# Mayfly_v1p0_revA3_public.net
KiCad netlist of a schematic drawn in EAGLE
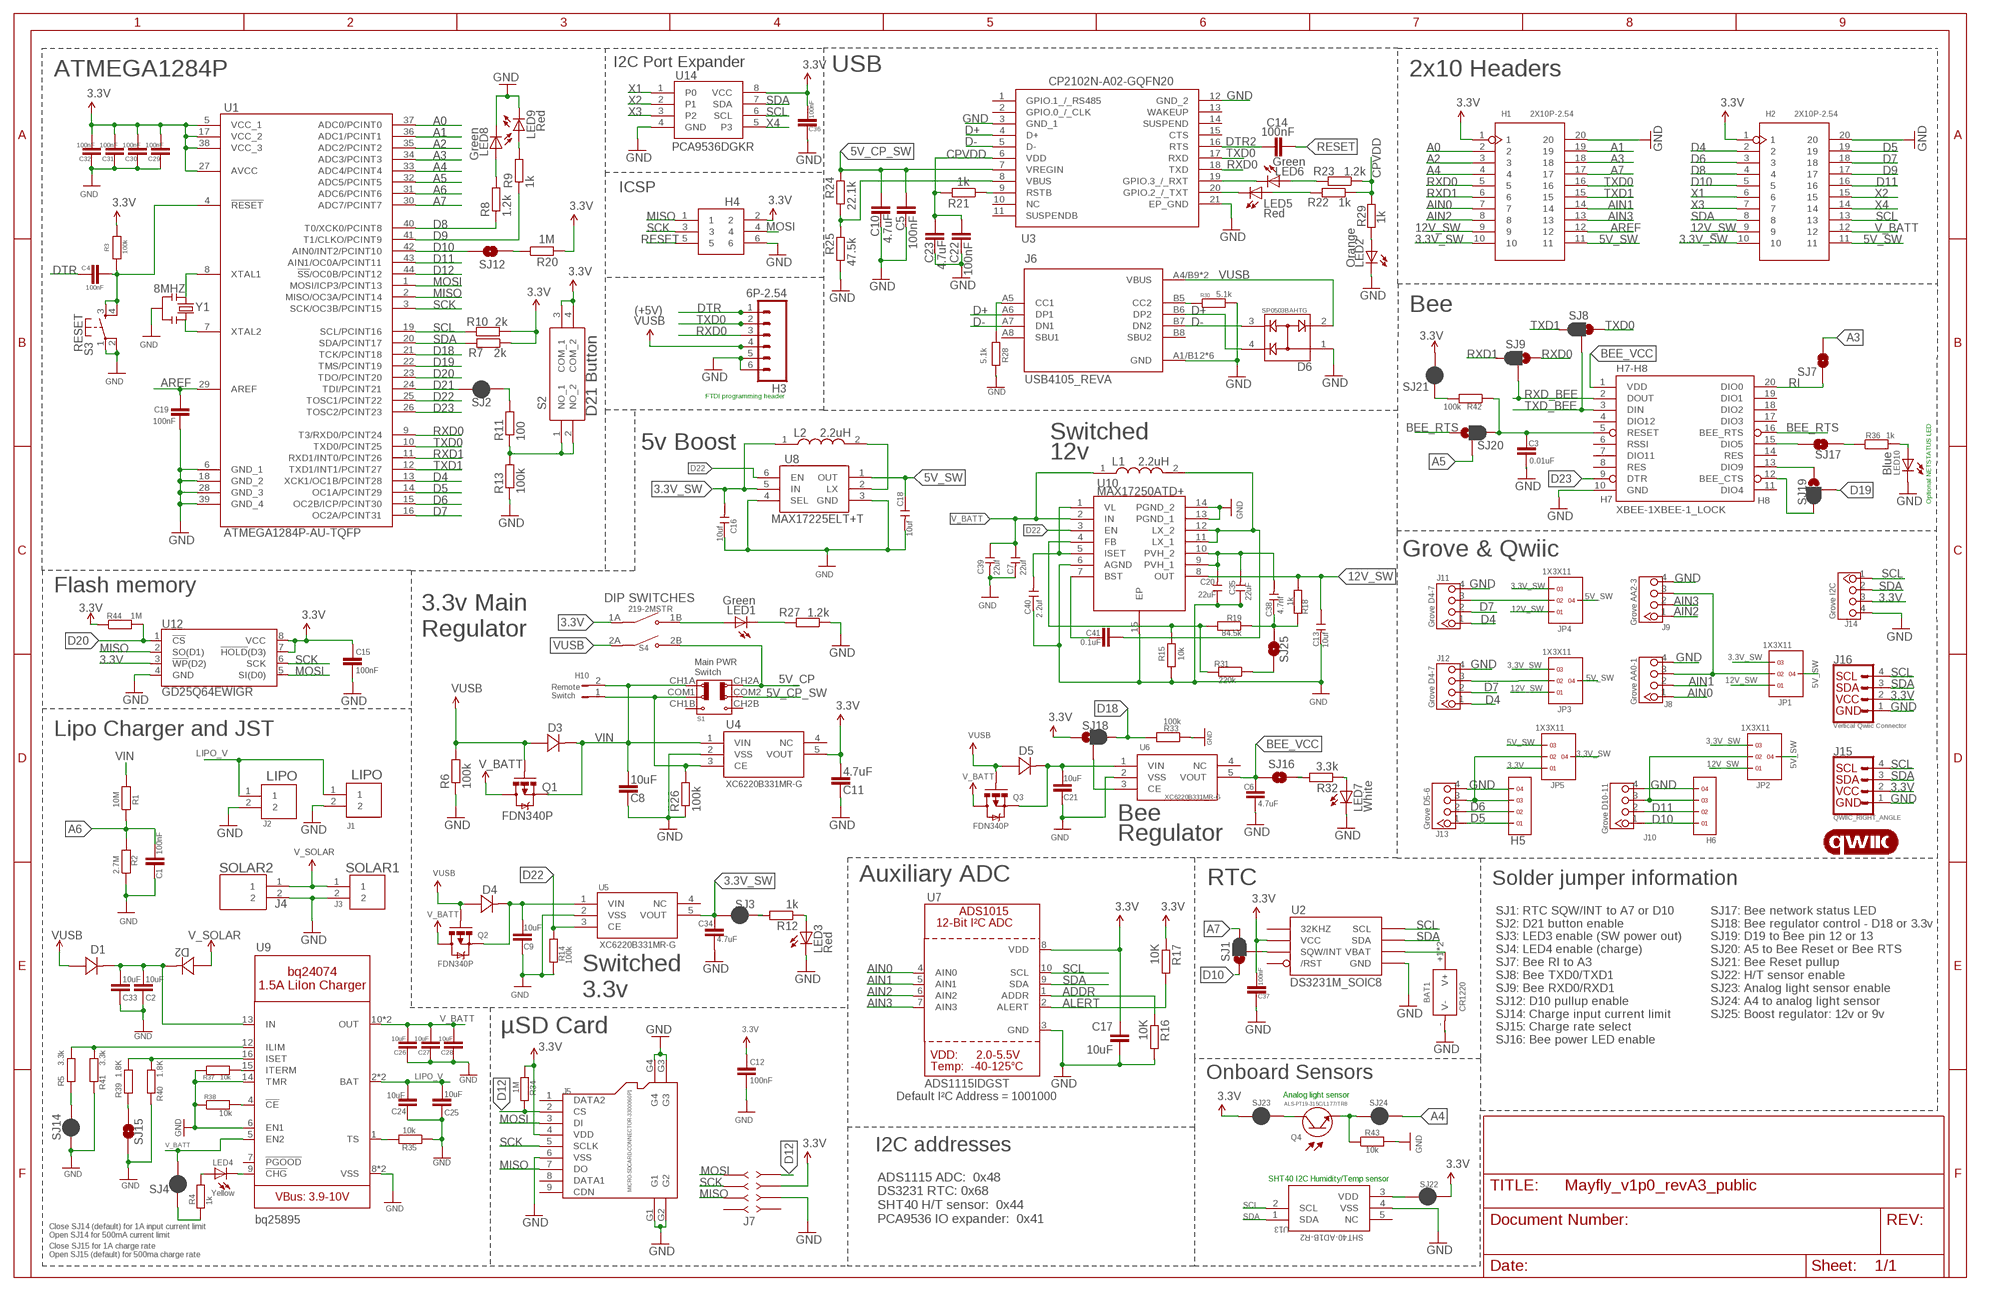
[diagram p0: schematic, sheet 1]

(export (version "E")
  (design (tool "Eeschema 10.0.6"))
  (components
    (comp (ref "BAT1")
      (value "CR1220")
      (footprint "eagle-import:BAT2P-13.5-CR1220")
      (libsource (lib "eagle-import") (part "DIP-BATTERY-CELL-HOLDER(1220)"))
    )
    (comp (ref "C1")
      (value "100nF")
      (footprint "eagle-import:C0603")
      (libsource (lib "eagle-import") (part "C_0603"))
    )
    (comp (ref "C2")
      (value "10uF")
      (footprint "eagle-import:C0603")
      (libsource (lib "eagle-import") (part "C_0603"))
    )
    (comp (ref "C3")
      (value "0.01uF")
      (footprint "eagle-import:C0603")
      (libsource (lib "eagle-import") (part "C_0603"))
    )
    (comp (ref "C4")
      (value "100nF")
      (footprint "eagle-import:C0603")
      (libsource (lib "eagle-import") (part "C_0603"))
    )
    (comp (ref "C5")
      (value "100nF")
      (footprint "eagle-import:C0603")
      (libsource (lib "eagle-import") (part "C_0603"))
    )
    (comp (ref "C6")
      (value "4.7uF")
      (footprint "eagle-import:C0603")
      (libsource (lib "eagle-import") (part "C_0603"))
    )
    (comp (ref "C7")
      (value "22uf")
      (footprint "eagle-import:C0805")
      (fields (field (name "MPN") "CC0805MKX5R5BB226"))
      (libsource (lib "eagle-import") (part "CERAMIC-22UF-6.3V-20%-X5R(0805)"))
    )
    (comp (ref "C8")
      (value "10uF")
      (footprint "eagle-import:C0603")
      (libsource (lib "eagle-import") (part "C_0603"))
    )
    (comp (ref "C9")
      (value "10uF")
      (footprint "eagle-import:C0603")
      (libsource (lib "eagle-import") (part "C_0603"))
    )
    (comp (ref "C10")
      (value "4.7uF")
      (footprint "eagle-import:C0603")
      (libsource (lib "eagle-import") (part "C_0603"))
    )
    (comp (ref "C11")
      (value "4.7uF")
      (footprint "eagle-import:C0603")
      (libsource (lib "eagle-import") (part "C_0603"))
    )
    (comp (ref "C12")
      (value "100nF")
      (footprint "eagle-import:C0603")
      (libsource (lib "eagle-import") (part "C_0603"))
    )
    (comp (ref "C13")
      (value "10uf")
      (footprint "eagle-import:C0805")
      (fields (field (name "MPN") "CC0805KKX5R8BB106"))
      (libsource (lib "eagle-import") (part "CERAMIC-10UF-25V-10%-X5R(0805)"))
    )
    (comp (ref "C14")
      (value "100nF")
      (footprint "eagle-import:C0603")
      (libsource (lib "eagle-import") (part "C_0603"))
    )
    (comp (ref "C15")
      (value "100nF")
      (footprint "eagle-import:C0402")
      (libsource (lib "eagle-import") (part "C_0402"))
    )
    (comp (ref "C16")
      (value "10uf")
      (footprint "eagle-import:C0603")
      (fields (field (name "MPN") "CC0603KRX5R6BB106"))
      (libsource (lib "eagle-import") (part "CERAMIC-10UF-10V-10%-X5R(0603)"))
    )
    (comp (ref "C17")
      (value "10uF")
      (footprint "eagle-import:C0603")
      (libsource (lib "eagle-import") (part "C_0603"))
    )
    (comp (ref "C18")
      (value "10uf")
      (footprint "eagle-import:C0603")
      (fields (field (name "MPN") "CC0603KRX5R6BB106"))
      (libsource (lib "eagle-import") (part "CERAMIC-10UF-10V-10%-X5R(0603)"))
    )
    (comp (ref "C19")
      (value "100nF")
      (footprint "eagle-import:C0402")
      (libsource (lib "eagle-import") (part "C_0402"))
    )
    (comp (ref "C20")
      (value "22uF")
      (footprint "eagle-import:C1206")
      (libsource (lib "eagle-import") (part "CERAMIC-22UF-16V-10%-X7R(1206)"))
    )
    (comp (ref "C21")
      (value "10uF")
      (footprint "eagle-import:C0603")
      (libsource (lib "eagle-import") (part "C_0603"))
    )
    (comp (ref "C22")
      (value "100nF")
      (footprint "eagle-import:C0603")
      (libsource (lib "eagle-import") (part "C_0603"))
    )
    (comp (ref "C23")
      (value "4.7uF")
      (footprint "eagle-import:C0603")
      (libsource (lib "eagle-import") (part "C_0603"))
    )
    (comp (ref "C24")
      (value "10uF")
      (footprint "eagle-import:C0603")
      (libsource (lib "eagle-import") (part "C_0603"))
    )
    (comp (ref "C25")
      (value "10uF")
      (footprint "eagle-import:C0603")
      (libsource (lib "eagle-import") (part "C_0603"))
    )
    (comp (ref "C26")
      (value "10uF")
      (footprint "eagle-import:C0603")
      (libsource (lib "eagle-import") (part "C_0603"))
    )
    (comp (ref "C27")
      (value "10uF")
      (footprint "eagle-import:C0603")
      (libsource (lib "eagle-import") (part "C_0603"))
    )
    (comp (ref "C28")
      (value "10uF")
      (footprint "eagle-import:C0603")
      (libsource (lib "eagle-import") (part "C_0603"))
    )
    (comp (ref "C29")
      (value "100nF")
      (footprint "eagle-import:C0603")
      (libsource (lib "eagle-import") (part "C_0603"))
    )
    (comp (ref "C30")
      (value "100nF")
      (footprint "eagle-import:C0603")
      (libsource (lib "eagle-import") (part "C_0603"))
    )
    (comp (ref "C31")
      (value "100nF")
      (footprint "eagle-import:C0603")
      (libsource (lib "eagle-import") (part "C_0603"))
    )
    (comp (ref "C32")
      (value "100nF")
      (footprint "eagle-import:C0603")
      (libsource (lib "eagle-import") (part "C_0603"))
    )
    (comp (ref "C33")
      (value "10uF")
      (footprint "eagle-import:C0603")
      (libsource (lib "eagle-import") (part "C_0603"))
    )
    (comp (ref "C34")
      (value "4.7uF")
      (footprint "eagle-import:C0603")
      (libsource (lib "eagle-import") (part "C_0603"))
    )
    (comp (ref "C35")
      (value "22uF")
      (footprint "eagle-import:C1206")
      (libsource (lib "eagle-import") (part "CERAMIC-22UF-16V-10%-X7R(1206)"))
    )
    (comp (ref "C36")
      (value "100nF")
      (footprint "eagle-import:C0603")
      (libsource (lib "eagle-import") (part "C_0603"))
    )
    (comp (ref "C37")
      (value "100nF")
      (footprint "eagle-import:C0603")
      (libsource (lib "eagle-import") (part "C_0603"))
    )
    (comp (ref "C38")
      (value "4.7nf")
      (footprint "eagle-import:C0603")
      (fields (field (name "MPN") "CC0603KRX7R9BB472"))
      (libsource (lib "eagle-import") (part "CERAMIC-4.7NF-50V-10%-X7R(0603)"))
    )
    (comp (ref "C39")
      (value "22uf")
      (footprint "eagle-import:C0805")
      (fields (field (name "MPN") "CC0805MKX5R5BB226"))
      (libsource (lib "eagle-import") (part "CERAMIC-22UF-6.3V-20%-X5R(0805)"))
    )
    (comp (ref "C40")
      (value "2.2uf")
      (footprint "eagle-import:C0805")
      (fields (field (name "MPN") "CC0805KKX7R8BB225"))
      (libsource (lib "eagle-import") (part "CERAMIC-2.2UF-25V-10%-X7R(0805)"))
    )
    (comp (ref "C41")
      (value "0.1uF")
      (footprint "eagle-import:C0402")
      (libsource (lib "eagle-import") (part "C_0402"))
    )
    (comp (ref "D1")
      (value "MSS2P2-M3/89A")
      (footprint "eagle-import:DIODE_MSP3V3")
      (libsource (lib "eagle-import") (part "MSS2P2-M3/89A"))
    )
    (comp (ref "D2")
      (value "MSS2P2-M3/89A")
      (footprint "eagle-import:DIODE_MSP3V3")
      (libsource (lib "eagle-import") (part "MSS2P2-M3/89A"))
    )
    (comp (ref "D3")
      (value "MSS2P2-M3/89A")
      (footprint "eagle-import:DIODE_MSP3V3")
      (libsource (lib "eagle-import") (part "MSS2P2-M3/89A"))
    )
    (comp (ref "D4")
      (value "MSS2P2-M3/89A")
      (footprint "eagle-import:DIODE_MSP3V3")
      (libsource (lib "eagle-import") (part "MSS2P2-M3/89A"))
    )
    (comp (ref "D5")
      (value "MSS2P2-M3/89A")
      (footprint "eagle-import:DIODE_MSP3V3")
      (libsource (lib "eagle-import") (part "MSS2P2-M3/89A"))
    )
    (comp (ref "D6")
      (value "SP0503BAHTG")
      (footprint "eagle-import:SOT143")
      (fields (field (name "DIGI-KEY_PART_NUMBER") "F2715CT-ND") (field (name "MF") "Littelfuse Inc."))
      (libsource (lib "eagle-import") (part "SP0503BAHTG"))
    )
    (comp (ref "H1")
      (value "2X10P-2.54")
      (footprint "eagle-import:H2X10-2.54")
      (fields (field (name "MPN") "F185-1210A0BA1"))
      (libsource (lib "eagle-import") (part "DIP-BLACK-FEMALE-HEADER(2X10P-2.54)-2.54"))
    )
    (comp (ref "H2")
      (value "2X10P-2.54")
      (footprint "eagle-import:H2X10-2.54")
      (fields (field (name "MPN") "F185-1210A0BA1"))
      (libsource (lib "eagle-import") (part "DIP-BLACK-FEMALE-HEADER(2X10P-2.54)-2.54"))
    )
    (comp (ref "H3")
      (value "6P-2.54")
      (footprint "eagle-import:1X06_FEMALE_LOCK.010")
      (libsource (lib "eagle-import") (part "M06FEMALE_LOCK"))
    )
    (comp (ref "H4")
      (value "FTSH-103-01-F-D")
      (footprint "eagle-import:FTSH-103-XX-YYY")
      (fields (field (name "MOUSER_PART_NUMBER") "200-FTSH10301FD"))
      (libsource (lib "eagle-import") (part "FTSH-103-01-F-D"))
    )
    (comp (ref "H5")
      (value "1X4")
      (footprint "eagle-import:1X4")
      (libsource (lib "eagle-import") (part "1X4"))
    )
    (comp (ref "H6")
      (value "1X4")
      (footprint "eagle-import:1X4")
      (libsource (lib "eagle-import") (part "1X4"))
    )
    (comp (ref "H7-H8")
      (value "XBEE-1XBEE-1_LOCK")
      (footprint "eagle-import:XBEE-1_LOCK")
      (libsource (lib "eagle-import") (part "XBEE-1XBEE-1_LOCK"))
    )
    (comp (ref "H10")
      (value "JUMPER-PTH-2-NO")
      (footprint "eagle-import:PTH-JUMPER-2-NO_NO_SILK")
      (libsource (lib "eagle-import") (part "JUMPER-PTH-2-NO"))
    )
    (comp (ref "J1")
      (value "JST_EPH_2PIN")
      (footprint "eagle-import:JST_EPH_B2B-PH-K-S")
      (libsource (lib "eagle-import") (part "JST_EPH_2PIN"))
    )
    (comp (ref "J2")
      (value "JST_EPH_2PIN")
      (footprint "eagle-import:JST_EPH_B2B-PH-K-S")
      (libsource (lib "eagle-import") (part "JST_EPH_2PIN"))
    )
    (comp (ref "J3")
      (value "JST_EPH_2PIN")
      (footprint "eagle-import:JST_EPH_B2B-PH-K-S")
      (libsource (lib "eagle-import") (part "JST_EPH_2PIN"))
    )
    (comp (ref "J4")
      (value "1778557")
      (footprint "eagle-import:SHDR2W70P0X250_1X2_670X500X765")
      (fields (field (name "MOUSER_PART_NUMBER") "651-1778557"))
      (libsource (lib "eagle-import") (part "1778557"))
    )
    (comp (ref "J5")
      (value "MICRO-SDCARD-CONNECTOR-3300060P1")
      (footprint "eagle-import:9P-SMD-W-RING")
      (libsource (lib "eagle-import") (part "MICRO-SDCARD-CONNECTOR-3300060P1"))
    )
    (comp (ref "J6")
      (value "USB4105_REVA")
      (footprint "eagle-import:GCT_USB4105_REVA")
      (fields (field (name "MF") "Global Connector Technology") (field (name "MP") "USB4105"))
      (libsource (lib "eagle-import") (part "USB4105_REVA"))
    )
    (comp (ref "J7")
      (value "79107-08_S")
      (footprint "eagle-import:79107-08")
      (libsource (lib "eagle-import") (part "79107-08_S"))
    )
    (comp (ref "J8")
      (value "Grove AA0-1")
      (footprint "eagle-import:HW4-2.0")
      (libsource (lib "eagle-import") (part "GROVE-CONNECTOR-DIP(4P-2.0)"))
    )
    (comp (ref "J9")
      (value "Grove AA2-3")
      (footprint "eagle-import:HW4-2.0")
      (libsource (lib "eagle-import") (part "GROVE-CONNECTOR-DIP(4P-2.0)"))
    )
    (comp (ref "J10")
      (value "Grove D10-11")
      (footprint "eagle-import:HW4-2.0")
      (libsource (lib "eagle-import") (part "GROVE-CONNECTOR-DIP(4P-2.0)"))
    )
    (comp (ref "J11")
      (value "Grove D4-7")
      (footprint "eagle-import:HW4-2.0")
      (libsource (lib "eagle-import") (part "GROVE-CONNECTOR-DIP(4P-2.0)"))
    )
    (comp (ref "J12")
      (value "Grove D4-7")
      (footprint "eagle-import:HW4-2.0")
      (libsource (lib "eagle-import") (part "GROVE-CONNECTOR-DIP(4P-2.0)"))
    )
    (comp (ref "J13")
      (value "Grove D5-6")
      (footprint "eagle-import:HW4-2.0")
      (libsource (lib "eagle-import") (part "GROVE-CONNECTOR-DIP(4P-2.0)"))
    )
    (comp (ref "J14")
      (value "Grove I2C")
      (footprint "eagle-import:HW4-2.0")
      (libsource (lib "eagle-import") (part "GROVE-CONNECTOR-DIP(4P-2.0)"))
    )
    (comp (ref "J15")
      (value "QWIIC_RIGHT_ANGLE")
      (footprint "eagle-import:JST04_1MM_RA")
      (libsource (lib "eagle-import") (part "QWIIC_CONNECTORJS-1MM"))
    )
    (comp (ref "J16")
      (value "Vertical Qwiic Connector")
      (footprint "eagle-import:JST04_1MM_VERT")
      (libsource (lib "eagle-import") (part "QWIIC_CONNECTOR"))
    )
    (comp (ref "JP1")
      (value "1X3X11")
      (footprint "eagle-import:1X3")
      (libsource (lib "eagle-import") (part "1X3X11X3X1"))
    )
    (comp (ref "JP2")
      (value "1X3X11")
      (footprint "eagle-import:1X3")
      (libsource (lib "eagle-import") (part "1X3X11X3X1"))
    )
    (comp (ref "JP3")
      (value "1X3X11")
      (footprint "eagle-import:1X3")
      (libsource (lib "eagle-import") (part "1X3X11X3X1"))
    )
    (comp (ref "JP4")
      (value "1X3X11")
      (footprint "eagle-import:1X3")
      (libsource (lib "eagle-import") (part "1X3X11X3X1"))
    )
    (comp (ref "JP5")
      (value "1X3X11")
      (footprint "eagle-import:1X3")
      (libsource (lib "eagle-import") (part "1X3X11X3X1"))
    )
    (comp (ref "L1")
      (value "2.2uH")
      (footprint "eagle-import:1285ASH1R0MP2")
      (fields
        (field (name "MANUFACTURER_PART_NUMBER") "DFE201610E-2R2M=P2")
        (field (name "MOUSER_PART_NUMBER") "81-DFE201610E-2R2MP2")
      )
      (libsource (lib "eagle-import") (part "DFE201610E-2R2M=P2"))
    )
    (comp (ref "L2")
      (value "2.2uH")
      (footprint "eagle-import:1285ASH1R0MP2")
      (fields
        (field (name "MANUFACTURER_PART_NUMBER") "DFE201610E-2R2M=P2")
        (field (name "MOUSER_PART_NUMBER") "81-DFE201610E-2R2MP2")
      )
      (libsource (lib "eagle-import") (part "DFE201610E-2R2M=P2"))
    )
    (comp (ref "LED1")
      (value "Green")
      (footprint "eagle-import:LED-0603")
      (libsource (lib "eagle-import") (part "LED0603"))
    )
    (comp (ref "LED2")
      (value "Orange")
      (footprint "eagle-import:LED-0603")
      (libsource (lib "eagle-import") (part "LED0603"))
    )
    (comp (ref "LED3")
      (value "Red")
      (footprint "eagle-import:LED-0603")
      (libsource (lib "eagle-import") (part "LED0603"))
    )
    (comp (ref "LED4")
      (value "Yellow")
      (footprint "eagle-import:LED-0603")
      (libsource (lib "eagle-import") (part "LED0603"))
    )
    (comp (ref "LED5")
      (value "Red")
      (footprint "eagle-import:LED-0603")
      (libsource (lib "eagle-import") (part "LED0603"))
    )
    (comp (ref "LED6")
      (value "Green")
      (footprint "eagle-import:LED-0603")
      (libsource (lib "eagle-import") (part "LED0603"))
    )
    (comp (ref "LED7")
      (value "White")
      (footprint "eagle-import:LED-0603")
      (libsource (lib "eagle-import") (part "LED0603"))
    )
    (comp (ref "LED8")
      (value "Green")
      (footprint "eagle-import:LED-0603")
      (libsource (lib "eagle-import") (part "LED0603"))
    )
    (comp (ref "LED9")
      (value "Red")
      (footprint "eagle-import:LED-0603")
      (libsource (lib "eagle-import") (part "LED0603"))
    )
    (comp (ref "LED10")
      (value "Blue")
      (footprint "eagle-import:LED-0603")
      (libsource (lib "eagle-import") (part "LED0603"))
    )
    (comp (ref "LOGO4")
      (value "QWIIC_LOGO_5MM")
      (footprint "eagle-import:QWIIC_5MM")
      (libsource (lib "eagle-import") (part "QWIIC_LOGO_5MM"))
    )
    (comp (ref "Q1")
      (value "FDN340P")
      (footprint "eagle-import:SOT23-S-PADS")
      (libsource (lib "eagle-import") (part "MOSFET-P-CHANNELSMALL"))
    )
    (comp (ref "Q2")
      (value "FDN340P")
      (footprint "eagle-import:SOT23-S-PADS")
      (libsource (lib "eagle-import") (part "MOSFET-P-CHANNELSMALL"))
    )
    (comp (ref "Q3")
      (value "FDN340P")
      (footprint "eagle-import:SOT23-S-PADS")
      (libsource (lib "eagle-import") (part "MOSFET-P-CHANNELSMALL"))
    )
    (comp (ref "Q4")
      (value "ALS-PT19-315C/L177/TR8")
      (footprint "eagle-import:XDCR_ALS-PT19-315C_L177_TR8")
      (fields (field (name "MF") "Everlight"))
      (libsource (lib "eagle-import") (part "ALS-PT19-315C/L177/TR8"))
    )
    (comp (ref "R1")
      (value "10M")
      (footprint "eagle-import:R0402")
      (libsource (lib "eagle-import") (part "R_0402"))
    )
    (comp (ref "R2")
      (value "2.7M")
      (footprint "eagle-import:R0402")
      (libsource (lib "eagle-import") (part "R_0402"))
    )
    (comp (ref "R3")
      (value "100k")
      (footprint "eagle-import:R0603")
      (libsource (lib "eagle-import") (part "R_0603"))
    )
    (comp (ref "R4")
      (value "1k")
      (footprint "eagle-import:R0402")
      (libsource (lib "eagle-import") (part "R_0402"))
    )
    (comp (ref "R5")
      (value "3.3k")
      (footprint "eagle-import:R0402")
      (libsource (lib "eagle-import") (part "R_0402"))
    )
    (comp (ref "R6")
      (value "100k")
      (footprint "eagle-import:R0402")
      (libsource (lib "eagle-import") (part "R_0402"))
    )
    (comp (ref "R7")
      (value "2k")
      (footprint "eagle-import:R0603")
      (libsource (lib "eagle-import") (part "R_0603"))
    )
    (comp (ref "R8")
      (value "1.2k")
      (footprint "eagle-import:R0402")
      (libsource (lib "eagle-import") (part "R_0402"))
    )
    (comp (ref "R9")
      (value "1k")
      (footprint "eagle-import:R0402")
      (libsource (lib "eagle-import") (part "R_0402"))
    )
    (comp (ref "R10")
      (value "2k")
      (footprint "eagle-import:R0603")
      (libsource (lib "eagle-import") (part "R_0603"))
    )
    (comp (ref "R11")
      (value "100")
      (footprint "eagle-import:R0402")
      (libsource (lib "eagle-import") (part "R_0402"))
    )
    (comp (ref "R12")
      (value "1k")
      (footprint "eagle-import:R0402")
      (libsource (lib "eagle-import") (part "R_0402"))
    )
    (comp (ref "R13")
      (value "100k")
      (footprint "eagle-import:R0402")
      (libsource (lib "eagle-import") (part "R_0402"))
    )
    (comp (ref "R14")
      (value "100k")
      (footprint "eagle-import:R0402")
      (libsource (lib "eagle-import") (part "R_0402"))
    )
    (comp (ref "R15")
      (value "10k")
      (footprint "eagle-import:R0402")
      (libsource (lib "eagle-import") (part "R_0402"))
    )
    (comp (ref "R16")
      (value "10K")
      (footprint "eagle-import:R0402")
      (libsource (lib "eagle-import") (part "R_0402"))
    )
    (comp (ref "R17")
      (value "10K")
      (footprint "eagle-import:R0402")
      (libsource (lib "eagle-import") (part "R_0402"))
    )
    (comp (ref "R18")
      (value "1k")
      (footprint "eagle-import:R0402")
      (libsource (lib "eagle-import") (part "R_0402"))
    )
    (comp (ref "R19")
      (value "84.5k")
      (footprint "eagle-import:R0402")
      (libsource (lib "eagle-import") (part "R_0402"))
    )
    (comp (ref "R20")
      (value "1M")
      (footprint "eagle-import:R0603")
      (libsource (lib "eagle-import") (part "R_0603"))
    )
    (comp (ref "R21")
      (value "1k")
      (footprint "eagle-import:R0402")
      (libsource (lib "eagle-import") (part "R_0402"))
    )
    (comp (ref "R22")
      (value "1k")
      (footprint "eagle-import:R0402")
      (libsource (lib "eagle-import") (part "R_0402"))
    )
    (comp (ref "R23")
      (value "1.2k")
      (footprint "eagle-import:R0402")
      (libsource (lib "eagle-import") (part "R_0402"))
    )
    (comp (ref "R24")
      (value "22.1k")
      (footprint "eagle-import:R0402")
      (libsource (lib "eagle-import") (part "R_0402"))
    )
    (comp (ref "R25")
      (value "47.5k")
      (footprint "eagle-import:R0402")
      (libsource (lib "eagle-import") (part "R_0402"))
    )
    (comp (ref "R26")
      (value "100k")
      (footprint "eagle-import:R0603")
      (libsource (lib "eagle-import") (part "R_0603"))
    )
    (comp (ref "R27")
      (value "1.2k")
      (footprint "eagle-import:R0402")
      (libsource (lib "eagle-import") (part "R_0402"))
    )
    (comp (ref "R28")
      (value "5.1k")
      (footprint "eagle-import:R0402")
      (libsource (lib "eagle-import") (part "R_0402"))
    )
    (comp (ref "R29")
      (value "1k")
      (footprint "eagle-import:R0402")
      (libsource (lib "eagle-import") (part "R_0402"))
    )
    (comp (ref "R30")
      (value "5.1k")
      (footprint "eagle-import:R0402")
      (libsource (lib "eagle-import") (part "R_0402"))
    )
    (comp (ref "R31")
      (value "220k")
      (footprint "eagle-import:R0402")
      (libsource (lib "eagle-import") (part "R_0402"))
    )
    (comp (ref "R32")
      (value "3.3k")
      (footprint "eagle-import:R0402")
      (libsource (lib "eagle-import") (part "R_0402"))
    )
    (comp (ref "R33")
      (value "100k")
      (footprint "eagle-import:R0402")
      (libsource (lib "eagle-import") (part "R_0402"))
    )
    (comp (ref "R34")
      (value "1M")
      (footprint "eagle-import:R0402")
      (libsource (lib "eagle-import") (part "R_0402"))
    )
    (comp (ref "R35")
      (value "10k")
      (footprint "eagle-import:R0402")
      (libsource (lib "eagle-import") (part "R_0402"))
    )
    (comp (ref "R36")
      (value "1k")
      (footprint "eagle-import:R0402")
      (libsource (lib "eagle-import") (part "R_0402"))
    )
    (comp (ref "R37")
      (value "10k")
      (footprint "eagle-import:R0402")
      (libsource (lib "eagle-import") (part "R_0402"))
    )
    (comp (ref "R38")
      (value "10k")
      (footprint "eagle-import:R0402")
      (libsource (lib "eagle-import") (part "R_0402"))
    )
    (comp (ref "R39")
      (value "1.8K")
      (footprint "eagle-import:R0402")
      (libsource (lib "eagle-import") (part "R_0402"))
    )
    (comp (ref "R40")
      (value "1.8K")
      (footprint "eagle-import:R0402")
      (libsource (lib "eagle-import") (part "R_0402"))
    )
    (comp (ref "R41")
      (value "3.3k")
      (footprint "eagle-import:R0402")
      (libsource (lib "eagle-import") (part "R_0402"))
    )
    (comp (ref "R42")
      (value "100k")
      (footprint "eagle-import:R0402")
      (libsource (lib "eagle-import") (part "R_0402"))
    )
    (comp (ref "R43")
      (value "10k")
      (footprint "eagle-import:R0402")
      (libsource (lib "eagle-import") (part "R_0402"))
    )
    (comp (ref "R44")
      (value "1M")
      (footprint "eagle-import:R0402")
      (libsource (lib "eagle-import") (part "R_0402"))
    )
    (comp (ref "S1")
      (value "SWITCH-2CH-6P-3010010P1")
      (footprint "eagle-import:6P-2CH-2.54-9.1X3.5X3.2+2H")
      (libsource (lib "eagle-import") (part "SWITCH-2CH-6P-3010010P1"))
    )
    (comp (ref "S2")
      (value "PTS647SK38SMTR2LFS")
      (footprint "eagle-import:PTS647SK38SMTR2LFS")
      (fields (field (name "MOUSER_PART_NUMBER") "611-PTS647SK38SMTR2L"))
      (libsource (lib "eagle-import") (part "PTS647SK38SMTR2LFS"))
    )
    (comp (ref "S3")
      (value "MOMENTARY-SWITCH-SPST-2-SMD-4.6X2.8MM")
      (footprint "eagle-import:TACTILE_SWITCH_SMD_4.6X2.8MM")
      (libsource (lib "eagle-import") (part "MOMENTARY-SWITCH-SPST-2-SMD-4.6X2.8MM"))
    )
    (comp (ref "S4")
      (value "219-2MSTR")
      (footprint "eagle-import:SW_219-2MSTR")
      (fields (field (name "DIGI-KEY_PART_NUMBER") "CT3114CT-ND") (field (name "MF") "CTS Electrocomponents"))
      (libsource (lib "eagle-import") (part "219-2MSTR"))
    )
    (comp (ref "SJ1")
      (value "JUMPER-SMT_3_1-NC_PASTE_SILK")
      (footprint "eagle-import:SMT-JUMPER_3_1-NC_PASTE_SILK")
      (libsource (lib "eagle-import") (part "JUMPER-SMT_3_1-NC_PASTE_SILK"))
    )
    (comp (ref "SJ2")
      (value "JUMPER-SMT_2_NC_PASTE_SILK")
      (footprint "eagle-import:SMT-JUMPER_2_NC_PASTE_SILK")
      (libsource (lib "eagle-import") (part "JUMPER-SMT_2_NC_PASTE_SILK"))
    )
    (comp (ref "SJ3")
      (value "JUMPER-SMT_2_NC_PASTE_SILK")
      (footprint "eagle-import:SMT-JUMPER_2_NC_PASTE_SILK")
      (libsource (lib "eagle-import") (part "JUMPER-SMT_2_NC_PASTE_SILK"))
    )
    (comp (ref "SJ4")
      (value "JUMPER-SMT_2_NC_PASTE_SILK")
      (footprint "eagle-import:SMT-JUMPER_2_NC_PASTE_SILK")
      (libsource (lib "eagle-import") (part "JUMPER-SMT_2_NC_PASTE_SILK"))
    )
    (comp (ref "SJ7")
      (value "JUMPER-SMT_2_NO_SILK")
      (footprint "eagle-import:SMT-JUMPER_2_NO_SILK")
      (libsource (lib "eagle-import") (part "JUMPER-SMT_2_NO_SILK"))
    )
    (comp (ref "SJ8")
      (value "JUMPER-SMT_3_1-NC_PASTE_SILK")
      (footprint "eagle-import:SMT-JUMPER_3_1-NC_PASTE_SILK")
      (libsource (lib "eagle-import") (part "JUMPER-SMT_3_1-NC_PASTE_SILK"))
    )
    (comp (ref "SJ9")
      (value "JUMPER-SMT_3_1-NC_PASTE_SILK")
      (footprint "eagle-import:SMT-JUMPER_3_1-NC_PASTE_SILK")
      (libsource (lib "eagle-import") (part "JUMPER-SMT_3_1-NC_PASTE_SILK"))
    )
    (comp (ref "SJ12")
      (value "SOLDERJUMPERNO")
      (footprint "eagle-import:SJ_2S-NO")
      (libsource (lib "eagle-import") (part "SOLDERJUMPERNO"))
    )
    (comp (ref "SJ14")
      (value "JUMPER-SMT_2_NC_PASTE_SILK")
      (footprint "eagle-import:SMT-JUMPER_2_NC_PASTE_SILK")
      (libsource (lib "eagle-import") (part "JUMPER-SMT_2_NC_PASTE_SILK"))
    )
    (comp (ref "SJ15")
      (value "JUMPER-SMT_2_NO_SILK")
      (footprint "eagle-import:SMT-JUMPER_2_NO_SILK")
      (libsource (lib "eagle-import") (part "JUMPER-SMT_2_NO_SILK"))
    )
    (comp (ref "SJ16")
      (value "JUMPER-SMT_2_NO_SILK")
      (footprint "eagle-import:SMT-JUMPER_2_NO_SILK")
      (libsource (lib "eagle-import") (part "JUMPER-SMT_2_NO_SILK"))
    )
    (comp (ref "SJ17")
      (value "JUMPER-SMT_2_NO_SILK")
      (footprint "eagle-import:SMT-JUMPER_2_NO_SILK")
      (libsource (lib "eagle-import") (part "JUMPER-SMT_2_NO_SILK"))
    )
    (comp (ref "SJ18")
      (value "JUMPER-SMT_3_1-NC_PASTE_SILK")
      (footprint "eagle-import:SMT-JUMPER_3_1-NC_PASTE_SILK")
      (libsource (lib "eagle-import") (part "JUMPER-SMT_3_1-NC_PASTE_SILK"))
    )
    (comp (ref "SJ19")
      (value "JUMPER-SMT_3_1-NC_PASTE_SILK")
      (footprint "eagle-import:SMT-JUMPER_3_1-NC_PASTE_SILK")
      (libsource (lib "eagle-import") (part "JUMPER-SMT_3_1-NC_PASTE_SILK"))
    )
    (comp (ref "SJ20")
      (value "JUMPER-SMT_3_1-NC_PASTE_SILK")
      (footprint "eagle-import:SMT-JUMPER_3_1-NC_PASTE_SILK")
      (libsource (lib "eagle-import") (part "JUMPER-SMT_3_1-NC_PASTE_SILK"))
    )
    (comp (ref "SJ21")
      (value "JUMPER-SMT_2_NC_PASTE_SILK")
      (footprint "eagle-import:SMT-JUMPER_2_NC_PASTE_SILK")
      (libsource (lib "eagle-import") (part "JUMPER-SMT_2_NC_PASTE_SILK"))
    )
    (comp (ref "SJ22")
      (value "JUMPER-SMT_2_NC_PASTE_SILK")
      (footprint "eagle-import:SMT-JUMPER_2_NC_PASTE_SILK")
      (libsource (lib "eagle-import") (part "JUMPER-SMT_2_NC_PASTE_SILK"))
    )
    (comp (ref "SJ23")
      (value "JUMPER-SMT_2_NC_PASTE_SILK")
      (footprint "eagle-import:SMT-JUMPER_2_NC_PASTE_SILK")
      (libsource (lib "eagle-import") (part "JUMPER-SMT_2_NC_PASTE_SILK"))
    )
    (comp (ref "SJ24")
      (value "JUMPER-SMT_2_NC_PASTE_SILK")
      (footprint "eagle-import:SMT-JUMPER_2_NC_PASTE_SILK")
      (libsource (lib "eagle-import") (part "JUMPER-SMT_2_NC_PASTE_SILK"))
    )
    (comp (ref "SJ25")
      (value "JUMPER-SMT_2_NO_SILK")
      (footprint "eagle-import:SMT-JUMPER_2_NO_SILK")
      (libsource (lib "eagle-import") (part "JUMPER-SMT_2_NO_SILK"))
    )
    (comp (ref "U1")
      (value "ATMEGA1284P-AU-TQFP")
      (footprint "eagle-import:QFP80P1200X1200X120-44N")
      (fields
        (field (name "MANUFACTURER_PART_NUMBER") "ATMEGA1284P-AU")
        (field (name "MOUSER_PART_NUMBER") "556-ATMEGA1284P-AU")
      )
      (libsource (lib "eagle-import") (part "ATMEGA1284P-AU-TQFP"))
    )
    (comp (ref "U2")
      (value "DS3231M_SOIC8")
      (footprint "eagle-import:SO8")
      (libsource (lib "eagle-import") (part "DS3231M_SOIC8"))
    )
    (comp (ref "U3")
      (value "CP2102N-A02-GQFN20")
      (footprint "eagle-import:CP2102NA02GQFN20")
      (fields (field (name "MOUSER_PART_NUMBER") "634-CP2102NA02GQFN20"))
      (libsource (lib "eagle-import") (part "CP2102N-A02-GQFN20"))
    )
    (comp (ref "U4")
      (value "XC6220B331MR-G")
      (footprint "eagle-import:SOT95P280X130-5N")
      (fields (field (name "MOUSER_PART_NUMBER") "865-XC6220B331MR-G"))
      (libsource (lib "eagle-import") (part "XC6220B331MR-G"))
    )
    (comp (ref "U5")
      (value "XC6220B331MR-G")
      (footprint "eagle-import:SOT95P280X130-5N")
      (fields (field (name "MOUSER_PART_NUMBER") "865-XC6220B331MR-G"))
      (libsource (lib "eagle-import") (part "XC6220B331MR-G"))
    )
    (comp (ref "U6")
      (value "XC6220B331MR-G")
      (footprint "eagle-import:SOT95P280X130-5N")
      (fields (field (name "MOUSER_PART_NUMBER") "865-XC6220B331MR-G"))
      (libsource (lib "eagle-import") (part "XC6220B331MR-G"))
    )
    (comp (ref "U7")
      (value "ADS1115IDGST")
      (footprint "eagle-import:MSOP10")
      (libsource (lib "eagle-import") (part "ADC_ADS1015"))
    )
    (comp (ref "U8")
      (value "MAX17225ELT+T")
      (footprint "eagle-import:MAX17225ELTT")
      (fields (field (name "MOUSER_PART_NUMBER") "700-MAX17225ELT+T"))
      (libsource (lib "eagle-import") (part "MAX17225ELT+T"))
    )
    (comp (ref "U9")
      (value "ADAFRUIT_POWER_BQ24074")
      (footprint "eagle-import:ADAFRUIT_POWER_QFN16_3MM")
      (libsource (lib "eagle-import") (part "ADAFRUIT_POWER_BQ24074"))
    )
    (comp (ref "U10")
      (value "MAX17250ATD+")
      (footprint "eagle-import:SON40P300X300X80-15N")
      (fields (field (name "MOUSER_PART_NUMBER") "700-MAX17250ATD+"))
      (libsource (lib "eagle-import") (part "MAX17250ATD+"))
    )
    (comp (ref "U12")
      (value "GD25Q64EWIGR")
      (footprint "eagle-import:WSON8-6X5MM")
      (libsource (lib "eagle-import") (part "W25Q32FVZP"))
    )
    (comp (ref "U13")
      (value "SHT40-AD1B-R2")
      (footprint "eagle-import:SHT4X_SEN")
      (fields (field (name "COPYRIGHT") "Copyright (C) 2018 Accelerated Designs. All rights reserved"))
      (libsource (lib "eagle-import") (part "SHT40-AD1B-R2"))
    )
    (comp (ref "U14")
      (value "PCA9536DGKR")
      (footprint "eagle-import:SOP65P490X110-8N")
      (fields (field (name "MOUSER_PART_NUMBER") "595-PCA9536DGKR"))
      (libsource (lib "eagle-import") (part "PCA9536DGKR"))
    )
    (comp (ref "Y1")
      (value "8MHZ")
      (footprint "eagle-import:X3-SMD-3.6X1.3X0.8MM")
      (fields (field (name "MPN") "CSTCE8M00G15L99-R0"))
      (libsource (lib "eagle-import") (part "SMD-RESONATOR-8MHZ-33PF-0.1%(3P-3.2X1.3MM)"))
    )
  )
  (nets
    (net (code "1") (name "/5V_CP") (class "Default")
      (node (ref "S1") (pin "CH2A") (pinfunction "CH2A_CH2A") (pintype "bidirectional"))
      (node (ref "S4") (pin "2B") (pinfunction "NO2_2B") (pintype "passive"))
    )
    (net (code "2") (name "/A0") (class "Default")
      (node (ref "H1") (pin "2") (pinfunction "2_2") (pintype "bidirectional"))
      (node (ref "U1") (pin "37") (pinfunction "ADC0/PCINT0_37") (pintype "bidirectional"))
    )
    (net (code "3") (name "/A1") (class "Default")
      (node (ref "H1") (pin "19") (pinfunction "19_19") (pintype "bidirectional"))
      (node (ref "U1") (pin "36") (pinfunction "ADC1/PCINT1_36") (pintype "bidirectional"))
    )
    (net (code "4") (name "/A2") (class "Default")
      (node (ref "H1") (pin "3") (pinfunction "3_3") (pintype "bidirectional"))
      (node (ref "U1") (pin "35") (pinfunction "ADC2/PCINT2_35") (pintype "bidirectional"))
    )
    (net (code "5") (name "/ADDR") (class "Default")
      (node (ref "R16") (pin "1") (pinfunction "1_1") (pintype "passive"))
      (node (ref "U7") (pin "1") (pinfunction "ADDR_1") (pintype "bidirectional"))
    )
    (net (code "6") (name "/AIN0") (class "Default")
      (node (ref "H1") (pin "7") (pinfunction "7_7") (pintype "bidirectional"))
      (node (ref "J8") (pin "1") (pinfunction "1_1") (pintype "bidirectional"))
      (node (ref "U7") (pin "4") (pinfunction "AIN0_4") (pintype "bidirectional"))
    )
    (net (code "7") (name "/AIN1") (class "Default")
      (node (ref "H1") (pin "14") (pinfunction "14_14") (pintype "bidirectional"))
      (node (ref "J8") (pin "2") (pinfunction "2_2") (pintype "bidirectional"))
      (node (ref "U7") (pin "5") (pinfunction "AIN1_5") (pintype "bidirectional"))
    )
    (net (code "8") (name "/AIN2") (class "Default")
      (node (ref "H1") (pin "8") (pinfunction "8_8") (pintype "bidirectional"))
      (node (ref "J9") (pin "1") (pinfunction "1_1") (pintype "bidirectional"))
      (node (ref "U7") (pin "6") (pinfunction "AIN2_6") (pintype "bidirectional"))
    )
    (net (code "9") (name "/AIN3") (class "Default")
      (node (ref "H1") (pin "13") (pinfunction "13_13") (pintype "bidirectional"))
      (node (ref "J9") (pin "2") (pinfunction "2_2") (pintype "bidirectional"))
      (node (ref "U7") (pin "7") (pinfunction "AIN3_7") (pintype "bidirectional"))
    )
    (net (code "10") (name "/ALERT") (class "Default")
      (node (ref "R17") (pin "2") (pinfunction "2_2") (pintype "passive"))
      (node (ref "U7") (pin "2") (pinfunction "ALERT_2") (pintype "bidirectional"))
    )
    (net (code "11") (name "/AREF") (class "Default")
      (node (ref "C19") (pin "2") (pinfunction "2_2") (pintype "passive"))
      (node (ref "H1") (pin "12") (pinfunction "12_12") (pintype "bidirectional"))
      (node (ref "U1") (pin "29") (pinfunction "AREF_29") (pintype "bidirectional"))
    )
    (net (code "12") (name "/BEE_RTS") (class "Default")
      (node (ref "H7-H8") (pin "16") (pinfunction "BEE_RTS_16") (pintype "input"))
      (node (ref "SJ20") (pin "1") (pinfunction "1_1") (pintype "passive"))
    )
    (net (code "13") (name "/CPVDD") (class "Default")
      (node (ref "C22") (pin "2") (pinfunction "2_2") (pintype "passive"))
      (node (ref "C23") (pin "2") (pinfunction "2_2") (pintype "passive"))
      (node (ref "R21") (pin "2") (pinfunction "2_2") (pintype "passive"))
      (node (ref "R22") (pin "1") (pinfunction "1_1") (pintype "passive"))
      (node (ref "R23") (pin "1") (pinfunction "1_1") (pintype "passive"))
      (node (ref "R29") (pin "1") (pinfunction "1_1") (pintype "passive"))
      (node (ref "U3") (pin "6") (pinfunction "VDD_6") (pintype "bidirectional"))
    )
    (net (code "14") (name "/D+") (class "Default")
      (node (ref "D6") (pin "4") (pinfunction "4_4") (pintype "passive"))
      (node (ref "J6") (pin "A6") (pinfunction "DP1_A6") (pintype "bidirectional"))
      (node (ref "J6") (pin "B6") (pinfunction "DP2_B6") (pintype "bidirectional"))
      (node (ref "U3") (pin "4") (pinfunction "D+_4") (pintype "bidirectional"))
    )
    (net (code "15") (name "/D-") (class "Default")
      (node (ref "D6") (pin "3") (pinfunction "3_3") (pintype "passive"))
      (node (ref "J6") (pin "A7") (pinfunction "DN1_A7") (pintype "bidirectional"))
      (node (ref "J6") (pin "B7") (pinfunction "DN2_B7") (pintype "bidirectional"))
      (node (ref "U3") (pin "5") (pinfunction "D-_5") (pintype "bidirectional"))
    )
    (net (code "16") (name "/D4") (class "Default")
      (node (ref "H2") (pin "2") (pinfunction "2_2") (pintype "bidirectional"))
      (node (ref "J11") (pin "1") (pinfunction "1_1") (pintype "bidirectional"))
      (node (ref "J12") (pin "1") (pinfunction "1_1") (pintype "bidirectional"))
      (node (ref "U1") (pin "13") (pinfunction "XCK1/OC1B/PCINT28_13") (pintype "bidirectional"))
    )
    (net (code "17") (name "/D5") (class "Default")
      (node (ref "H2") (pin "19") (pinfunction "19_19") (pintype "bidirectional"))
      (node (ref "H5") (pin "1") (pinfunction "1_1") (pintype "bidirectional"))
      (node (ref "J13") (pin "1") (pinfunction "1_1") (pintype "bidirectional"))
      (node (ref "U1") (pin "14") (pinfunction "OC1A/PCINT29_14") (pintype "bidirectional"))
    )
    (net (code "18") (name "/D6") (class "Default")
      (node (ref "H2") (pin "3") (pinfunction "3_3") (pintype "bidirectional"))
      (node (ref "H5") (pin "2") (pinfunction "2_2") (pintype "bidirectional"))
      (node (ref "J13") (pin "2") (pinfunction "2_2") (pintype "bidirectional"))
      (node (ref "U1") (pin "15") (pinfunction "OC2B/ICP/PCINT30_15") (pintype "bidirectional"))
    )
    (net (code "19") (name "/D7") (class "Default")
      (node (ref "H2") (pin "18") (pinfunction "18_18") (pintype "bidirectional"))
      (node (ref "J11") (pin "2") (pinfunction "2_2") (pintype "bidirectional"))
      (node (ref "J12") (pin "2") (pinfunction "2_2") (pintype "bidirectional"))
      (node (ref "U1") (pin "16") (pinfunction "OC2A/PCINT31_16") (pintype "bidirectional"))
    )
    (net (code "20") (name "/D8") (class "Default")
      (node (ref "H2") (pin "4") (pinfunction "4_4") (pintype "bidirectional"))
      (node (ref "R8") (pin "1") (pinfunction "1_1") (pintype "passive"))
      (node (ref "U1") (pin "40") (pinfunction "T0/XCK0/PCINT8_40") (pintype "bidirectional"))
    )
    (net (code "21") (name "/D9") (class "Default")
      (node (ref "H2") (pin "17") (pinfunction "17_17") (pintype "bidirectional"))
      (node (ref "R9") (pin "1") (pinfunction "1_1") (pintype "passive"))
      (node (ref "U1") (pin "41") (pinfunction "T1/CLKO/PCINT9_41") (pintype "bidirectional"))
    )
    (net (code "22") (name "/D11") (class "Default")
      (node (ref "H2") (pin "16") (pinfunction "16_16") (pintype "bidirectional"))
      (node (ref "H6") (pin "2") (pinfunction "2_2") (pintype "bidirectional"))
      (node (ref "J10") (pin "2") (pinfunction "2_2") (pintype "bidirectional"))
      (node (ref "U1") (pin "43") (pinfunction "AIN1/OC0A/PCINT11_43") (pintype "bidirectional"))
    )
    (net (code "23") (name "/D21") (class "Default")
      (node (ref "SJ2") (pin "2") (pinfunction "2_2") (pintype "passive"))
      (node (ref "U1") (pin "24") (pinfunction "TDI/PCINT21_24") (pintype "bidirectional"))
    )
    (net (code "24") (name "/DTR") (class "Default")
      (node (ref "C4") (pin "1") (pinfunction "1_1") (pintype "passive"))
      (node (ref "H3") (pin "1") (pinfunction "1_1") (pintype "passive"))
    )
    (net (code "25") (name "/DTR2") (class "Default")
      (node (ref "C14") (pin "2") (pinfunction "2_2") (pintype "passive"))
      (node (ref "U3") (pin "16") (pinfunction "RTS_16") (pintype "bidirectional"))
    )
    (net (code "26") (name "/LIPO_V") (class "Default")
      (node (ref "C24") (pin "2") (pinfunction "2_2") (pintype "passive"))
      (node (ref "C25") (pin "2") (pinfunction "2_2") (pintype "passive"))
      (node (ref "J1") (pin "1") (pinfunction "1_1") (pintype "bidirectional"))
      (node (ref "J2") (pin "1") (pinfunction "1_1") (pintype "bidirectional"))
      (node (ref "U9") (pin "2") (pinfunction "BAT_2") (pintype "input"))
      (node (ref "U9") (pin "3") (pinfunction "BAT_3") (pintype "input"))
    )
    (net (code "27") (name "/MISO") (class "Default")
      (node (ref "H4") (pin "1") (pinfunction "1_1") (pintype "bidirectional"))
      (node (ref "J5") (pin "7") (pinfunction "DO_7") (pintype "bidirectional"))
      (node (ref "J7") (pin "6") (pinfunction "J_6") (pintype "passive"))
      (node (ref "U1") (pin "2") (pinfunction "MISO/OC3A/PCINT14_2") (pintype "bidirectional"))
      (node (ref "U12") (pin "2") (pinfunction "SO(D1)_2") (pintype "bidirectional"))
    )
    (net (code "28") (name "/MOSI") (class "Default")
      (node (ref "H4") (pin "4") (pinfunction "4_4") (pintype "bidirectional"))
      (node (ref "J5") (pin "3") (pinfunction "DI_3") (pintype "bidirectional"))
      (node (ref "J7") (pin "2") (pinfunction "J_2") (pintype "passive"))
      (node (ref "U1") (pin "1") (pinfunction "MOSI/ICP3/PCINT13_1") (pintype "bidirectional"))
      (node (ref "U12") (pin "5") (pinfunction "SI(D0)_5") (pintype "bidirectional"))
    )
    (net (code "29") (name "/RI") (class "Default")
      (node (ref "H7-H8") (pin "20") (pinfunction "DIO0_20") (pintype "bidirectional"))
      (node (ref "SJ7") (pin "1") (pinfunction "1_1") (pintype "passive"))
    )
    (net (code "30") (name "/RXD0") (class "Default")
      (node (ref "H1") (pin "5") (pinfunction "5_5") (pintype "bidirectional"))
      (node (ref "H3") (pin "3") (pinfunction "3_3") (pintype "passive"))
      (node (ref "SJ9") (pin "1") (pinfunction "1_1") (pintype "passive"))
      (node (ref "U1") (pin "9") (pinfunction "T3/RXD0/PCINT24_9") (pintype "bidirectional"))
      (node (ref "U3") (pin "18") (pinfunction "TXD_18") (pintype "bidirectional"))
    )
    (net (code "31") (name "/RXD1") (class "Default")
      (node (ref "H1") (pin "6") (pinfunction "6_6") (pintype "bidirectional"))
      (node (ref "SJ9") (pin "3") (pinfunction "3_3") (pintype "passive"))
      (node (ref "U1") (pin "11") (pinfunction "RXD1/INT0/PCINT26_11") (pintype "bidirectional"))
    )
    (net (code "32") (name "/RXD_BEE") (class "Default")
      (node (ref "H7-H8") (pin "2") (pinfunction "DOUT_2") (pintype "output"))
      (node (ref "SJ9") (pin "2") (pinfunction "2_2") (pintype "passive"))
    )
    (net (code "33") (name "/SCK") (class "Default")
      (node (ref "H4") (pin "3") (pinfunction "3_3") (pintype "bidirectional"))
      (node (ref "J5") (pin "5") (pinfunction "SCLK_5") (pintype "bidirectional"))
      (node (ref "J7") (pin "4") (pinfunction "J_4") (pintype "passive"))
      (node (ref "U1") (pin "3") (pinfunction "SCK/OC3B/PCINT15_3") (pintype "bidirectional"))
      (node (ref "U12") (pin "6") (pinfunction "SCK_6") (pintype "bidirectional"))
    )
    (net (code "34") (name "/SCL") (class "Default")
      (node (ref "H2") (pin "13") (pinfunction "13_13") (pintype "bidirectional"))
      (node (ref "J14") (pin "1") (pinfunction "1_1") (pintype "bidirectional"))
      (node (ref "J15") (pin "4") (pinfunction "4_4") (pintype "passive"))
      (node (ref "J16") (pin "4") (pinfunction "4_4") (pintype "passive"))
      (node (ref "R10") (pin "1") (pinfunction "1_1") (pintype "passive"))
      (node (ref "U1") (pin "19") (pinfunction "SCL/PCINT16_19") (pintype "bidirectional"))
      (node (ref "U13") (pin "2") (pinfunction "SCL_2") (pintype "input"))
      (node (ref "U14") (pin "6") (pinfunction "SCL_6") (pintype "bidirectional"))
      (node (ref "U2") (pin "8") (pinfunction "SCL_8") (pintype "bidirectional"))
      (node (ref "U7") (pin "10") (pinfunction "SCL_10") (pintype "bidirectional"))
    )
    (net (code "35") (name "/SDA") (class "Default")
      (node (ref "H2") (pin "8") (pinfunction "8_8") (pintype "bidirectional"))
      (node (ref "J14") (pin "2") (pinfunction "2_2") (pintype "bidirectional"))
      (node (ref "J15") (pin "3") (pinfunction "3_3") (pintype "passive"))
      (node (ref "J16") (pin "3") (pinfunction "3_3") (pintype "passive"))
      (node (ref "R7") (pin "2") (pinfunction "2_2") (pintype "passive"))
      (node (ref "U1") (pin "20") (pinfunction "SDA/PCINT17_20") (pintype "bidirectional"))
      (node (ref "U13") (pin "1") (pinfunction "SDA_1") (pintype "bidirectional"))
      (node (ref "U14") (pin "7") (pinfunction "SDA_7") (pintype "bidirectional"))
      (node (ref "U2") (pin "7") (pinfunction "SDA_7") (pintype "bidirectional"))
      (node (ref "U7") (pin "9") (pinfunction "SDA_9") (pintype "bidirectional"))
    )
    (net (code "36") (name "/TXD0") (class "Default")
      (node (ref "H1") (pin "16") (pinfunction "16_16") (pintype "bidirectional"))
      (node (ref "H3") (pin "2") (pinfunction "2_2") (pintype "passive"))
      (node (ref "SJ8") (pin "1") (pinfunction "1_1") (pintype "passive"))
      (node (ref "U1") (pin "10") (pinfunction "TXD0/PCINT25_10") (pintype "bidirectional"))
      (node (ref "U3") (pin "17") (pinfunction "RXD_17") (pintype "bidirectional"))
    )
    (net (code "37") (name "/TXD1") (class "Default")
      (node (ref "H1") (pin "15") (pinfunction "15_15") (pintype "bidirectional"))
      (node (ref "SJ8") (pin "3") (pinfunction "3_3") (pintype "passive"))
      (node (ref "U1") (pin "12") (pinfunction "TXD1/INT1/PCINT27_12") (pintype "bidirectional"))
    )
    (net (code "38") (name "/TXD_BEE") (class "Default")
      (node (ref "H7-H8") (pin "3") (pinfunction "DIN_3") (pintype "input"))
      (node (ref "SJ8") (pin "2") (pinfunction "2_2") (pintype "passive"))
    )
    (net (code "39") (name "/VIN") (class "Default")
      (node (ref "C8") (pin "2") (pinfunction "2_2") (pintype "passive"))
      (node (ref "D3") (pin "1") (pinfunction "1_1") (pintype "passive"))
      (node (ref "H10") (pin "2") (pinfunction "2_2") (pintype "passive"))
      (node (ref "Q1") (pin "2") (pinfunction "S_2") (pintype "passive"))
      (node (ref "R1") (pin "2") (pinfunction "2_2") (pintype "passive"))
      (node (ref "S1") (pin "CH1A") (pinfunction "CH1A_CH1A") (pintype "bidirectional"))
      (node (ref "U4") (pin "1") (pinfunction "VIN_1") (pintype "bidirectional"))
    )
    (net (code "40") (name "/X1") (class "Default")
      (node (ref "H2") (pin "6") (pinfunction "6_6") (pintype "bidirectional"))
      (node (ref "U14") (pin "1") (pinfunction "P0_1") (pintype "bidirectional"))
    )
    (net (code "41") (name "/X2") (class "Default")
      (node (ref "H2") (pin "15") (pinfunction "15_15") (pintype "bidirectional"))
      (node (ref "U14") (pin "2") (pinfunction "P1_2") (pintype "bidirectional"))
    )
    (net (code "42") (name "/X3") (class "Default")
      (node (ref "H2") (pin "7") (pinfunction "7_7") (pintype "bidirectional"))
      (node (ref "U14") (pin "3") (pinfunction "P2_3") (pintype "bidirectional"))
    )
    (net (code "43") (name "/X4") (class "Default")
      (node (ref "H2") (pin "14") (pinfunction "14_14") (pintype "bidirectional"))
      (node (ref "U14") (pin "5") (pinfunction "P3_5") (pintype "bidirectional"))
    )
    (net (code "44") (name "3.3V") (class "Default")
      (node (ref "C11") (pin "2") (pinfunction "2_2") (pintype "passive"))
      (node (ref "C12") (pin "2") (pinfunction "2_2") (pintype "passive"))
      (node (ref "C15") (pin "2") (pinfunction "2_2") (pintype "passive"))
      (node (ref "C17") (pin "1") (pinfunction "1_1") (pintype "passive"))
      (node (ref "C29") (pin "2") (pinfunction "2_2") (pintype "passive"))
      (node (ref "C30") (pin "2") (pinfunction "2_2") (pintype "passive"))
      (node (ref "C31") (pin "2") (pinfunction "2_2") (pintype "passive"))
      (node (ref "C32") (pin "2") (pinfunction "2_2") (pintype "passive"))
      (node (ref "C36") (pin "2") (pinfunction "2_2") (pintype "passive"))
      (node (ref "C37") (pin "2") (pinfunction "2_2") (pintype "passive"))
      (node (ref "H1") (pin "1") (pinfunction "1_1") (pintype "bidirectional"))
      (node (ref "H2") (pin "1") (pinfunction "1_1") (pintype "bidirectional"))
      (node (ref "H4") (pin "2") (pinfunction "2_2") (pintype "bidirectional"))
      (node (ref "J14") (pin "3") (pinfunction "3_3") (pintype "bidirectional"))
      (node (ref "J15") (pin "2") (pinfunction "2_2") (pintype "power_in"))
      (node (ref "J16") (pin "2") (pinfunction "2_2") (pintype "power_in"))
      (node (ref "J5") (pin "4") (pinfunction "VDD_4") (pintype "bidirectional"))
      (node (ref "J7") (pin "3") (pinfunction "J_3") (pintype "passive"))
      (node (ref "JP5") (pin "1") (pinfunction "1_1") (pintype "bidirectional"))
      (node (ref "R10") (pin "2") (pinfunction "2_2") (pintype "passive"))
      (node (ref "R17") (pin "1") (pinfunction "1_1") (pintype "passive"))
      (node (ref "R20") (pin "2") (pinfunction "2_2") (pintype "passive"))
      (node (ref "R3") (pin "2") (pinfunction "2_2") (pintype "passive"))
      (node (ref "R34") (pin "1") (pinfunction "1_1") (pintype "passive"))
      (node (ref "R44") (pin "1") (pinfunction "1_1") (pintype "passive"))
      (node (ref "R7") (pin "1") (pinfunction "1_1") (pintype "passive"))
      (node (ref "S2") (pin "3") (pinfunction "COM_1_3") (pintype "bidirectional"))
      (node (ref "S2") (pin "4") (pinfunction "COM_2_4") (pintype "bidirectional"))
      (node (ref "S4") (pin "1A") (pinfunction "COM1_1A") (pintype "passive"))
      (node (ref "SJ18") (pin "1") (pinfunction "1_1") (pintype "passive"))
      (node (ref "SJ21") (pin "2") (pinfunction "2_2") (pintype "passive"))
      (node (ref "SJ22") (pin "1") (pinfunction "1_1") (pintype "passive"))
      (node (ref "SJ23") (pin "1") (pinfunction "1_1") (pintype "passive"))
      (node (ref "U1") (pin "17") (pinfunction "VCC_2_17") (pintype "bidirectional"))
      (node (ref "U1") (pin "27") (pinfunction "AVCC_27") (pintype "bidirectional"))
      (node (ref "U1") (pin "38") (pinfunction "VCC_3_38") (pintype "bidirectional"))
      (node (ref "U1") (pin "5") (pinfunction "VCC_1_5") (pintype "bidirectional"))
      (node (ref "U12") (pin "3") (pinfunction "~{WP}(D2)_3") (pintype "bidirectional"))
      (node (ref "U12") (pin "7") (pinfunction "~{HOLD}(D3)_7") (pintype "bidirectional"))
      (node (ref "U12") (pin "8") (pinfunction "VCC_8") (pintype "bidirectional"))
      (node (ref "U14") (pin "8") (pinfunction "VCC_8") (pintype "bidirectional"))
      (node (ref "U2") (pin "2") (pinfunction "VCC_2") (pintype "bidirectional"))
      (node (ref "U4") (pin "5") (pinfunction "VOUT_5") (pintype "bidirectional"))
      (node (ref "U7") (pin "8") (pinfunction "VDD_8") (pintype "bidirectional"))
    )
    (net (code "45") (name "3.3V_SW") (class "Default")
      (node (ref "C16") (pin "2") (pinfunction "2_2") (pintype "passive"))
      (node (ref "C34") (pin "2") (pinfunction "2_2") (pintype "passive"))
      (node (ref "H1") (pin "10") (pinfunction "10_10") (pintype "bidirectional"))
      (node (ref "H2") (pin "10") (pinfunction "10_10") (pintype "bidirectional"))
      (node (ref "JP1") (pin "3") (pinfunction "3_3") (pintype "bidirectional"))
      (node (ref "JP2") (pin "3") (pinfunction "3_3") (pintype "bidirectional"))
      (node (ref "JP3") (pin "3") (pinfunction "3_3") (pintype "bidirectional"))
      (node (ref "JP4") (pin "3") (pinfunction "3_3") (pintype "bidirectional"))
      (node (ref "JP5") (pin "4") (pinfunction "4_4") (pintype "bidirectional"))
      (node (ref "L2") (pin "1") (pinfunction "1_1") (pintype "bidirectional"))
      (node (ref "SJ3") (pin "1") (pinfunction "1_1") (pintype "passive"))
      (node (ref "U5") (pin "5") (pinfunction "VOUT_5") (pintype "bidirectional"))
      (node (ref "U8") (pin "5") (pinfunction "IN_5") (pintype "bidirectional"))
    )
    (net (code "46") (name "5V_CP_SW") (class "Default")
      (node (ref "C10") (pin "2") (pinfunction "2_2") (pintype "passive"))
      (node (ref "C5") (pin "2") (pinfunction "2_2") (pintype "passive"))
      (node (ref "R24") (pin "2") (pinfunction "2_2") (pintype "passive"))
      (node (ref "S1") (pin "COM2") (pinfunction "COM2_COM2") (pintype "bidirectional"))
      (node (ref "U3") (pin "7") (pinfunction "VREGIN_7") (pintype "bidirectional"))
    )
    (net (code "47") (name "5V_SW") (class "Default")
      (node (ref "C18") (pin "1") (pinfunction "1_1") (pintype "passive"))
      (node (ref "H1") (pin "11") (pinfunction "11_11") (pintype "bidirectional"))
      (node (ref "H2") (pin "11") (pinfunction "11_11") (pintype "bidirectional"))
      (node (ref "JP1") (pin "4") (pinfunction "4_4") (pintype "bidirectional"))
      (node (ref "JP2") (pin "4") (pinfunction "4_4") (pintype "bidirectional"))
      (node (ref "JP3") (pin "4") (pinfunction "4_4") (pintype "bidirectional"))
      (node (ref "JP4") (pin "4") (pinfunction "4_4") (pintype "bidirectional"))
      (node (ref "JP5") (pin "3") (pinfunction "3_3") (pintype "bidirectional"))
      (node (ref "U8") (pin "1") (pinfunction "OUT_1") (pintype "bidirectional"))
    )
    (net (code "48") (name "12V_SW") (class "Default")
      (node (ref "C13") (pin "1") (pinfunction "1_1") (pintype "passive"))
      (node (ref "H1") (pin "9") (pinfunction "9_9") (pintype "bidirectional"))
      (node (ref "H2") (pin "9") (pinfunction "9_9") (pintype "bidirectional"))
      (node (ref "JP1") (pin "1") (pinfunction "1_1") (pintype "bidirectional"))
      (node (ref "JP2") (pin "1") (pinfunction "1_1") (pintype "bidirectional"))
      (node (ref "JP3") (pin "1") (pinfunction "1_1") (pintype "bidirectional"))
      (node (ref "JP4") (pin "1") (pinfunction "1_1") (pintype "bidirectional"))
      (node (ref "R18") (pin "1") (pinfunction "1_1") (pintype "passive"))
      (node (ref "U10") (pin "8") (pinfunction "OUT_8") (pintype "bidirectional"))
    )
    (net (code "49") (name "A3") (class "Default")
      (node (ref "H1") (pin "18") (pinfunction "18_18") (pintype "bidirectional"))
      (node (ref "SJ7") (pin "2") (pinfunction "2_2") (pintype "passive"))
      (node (ref "U1") (pin "34") (pinfunction "ADC3/PCINT3_34") (pintype "bidirectional"))
    )
    (net (code "50") (name "A4") (class "Default")
      (node (ref "H1") (pin "4") (pinfunction "4_4") (pintype "bidirectional"))
      (node (ref "SJ24") (pin "2") (pinfunction "2_2") (pintype "passive"))
      (node (ref "U1") (pin "33") (pinfunction "ADC4/PCINT4_33") (pintype "bidirectional"))
    )
    (net (code "51") (name "A5") (class "Default")
      (node (ref "SJ20") (pin "2") (pinfunction "2_2") (pintype "passive"))
      (node (ref "U1") (pin "32") (pinfunction "ADC5/PCINT5_32") (pintype "bidirectional"))
    )
    (net (code "52") (name "A6") (class "Default")
      (node (ref "C1") (pin "2") (pinfunction "2_2") (pintype "passive"))
      (node (ref "R1") (pin "1") (pinfunction "1_1") (pintype "passive"))
      (node (ref "R2") (pin "2") (pinfunction "2_2") (pintype "passive"))
      (node (ref "U1") (pin "31") (pinfunction "ADC6/PCINT6_31") (pintype "bidirectional"))
    )
    (net (code "53") (name "A7") (class "Default")
      (node (ref "H1") (pin "17") (pinfunction "17_17") (pintype "bidirectional"))
      (node (ref "SJ1") (pin "3") (pinfunction "3_3") (pintype "passive"))
      (node (ref "U1") (pin "30") (pinfunction "ADC7/PCINT7_30") (pintype "bidirectional"))
    )
    (net (code "54") (name "BEE_VCC") (class "Default")
      (node (ref "C6") (pin "2") (pinfunction "2_2") (pintype "passive"))
      (node (ref "H7-H8") (pin "1") (pinfunction "VDD_1") (pintype "power_in"))
      (node (ref "SJ16") (pin "1") (pinfunction "1_1") (pintype "passive"))
      (node (ref "U6") (pin "5") (pinfunction "VOUT_5") (pintype "bidirectional"))
    )
    (net (code "55") (name "D10") (class "Default")
      (node (ref "H2") (pin "5") (pinfunction "5_5") (pintype "bidirectional"))
      (node (ref "H6") (pin "1") (pinfunction "1_1") (pintype "bidirectional"))
      (node (ref "J10") (pin "1") (pinfunction "1_1") (pintype "bidirectional"))
      (node (ref "SJ1") (pin "1") (pinfunction "1_1") (pintype "passive"))
      (node (ref "SJ12") (pin "1") (pinfunction "1_1") (pintype "passive"))
      (node (ref "U1") (pin "42") (pinfunction "AIN0/INT2/PCINT10_42") (pintype "bidirectional"))
    )
    (net (code "56") (name "D12") (class "Default")
      (node (ref "J5") (pin "2") (pinfunction "CS_2") (pintype "bidirectional"))
      (node (ref "J7") (pin "1") (pinfunction "J_1") (pintype "passive"))
      (node (ref "R34") (pin "2") (pinfunction "2_2") (pintype "passive"))
      (node (ref "U1") (pin "44") (pinfunction "~{SS}/OC0B/PCINT12_44") (pintype "bidirectional"))
    )
    (net (code "57") (name "D18") (class "Default")
      (node (ref "R33") (pin "2") (pinfunction "2_2") (pintype "passive"))
      (node (ref "SJ18") (pin "3") (pinfunction "3_3") (pintype "passive"))
      (node (ref "U1") (pin "21") (pinfunction "TCK/PCINT18_21") (pintype "bidirectional"))
    )
    (net (code "58") (name "D19") (class "Default")
      (node (ref "SJ19") (pin "2") (pinfunction "2_2") (pintype "passive"))
      (node (ref "U1") (pin "22") (pinfunction "TMS/PCINT19_22") (pintype "bidirectional"))
    )
    (net (code "59") (name "D20") (class "Default")
      (node (ref "R44") (pin "2") (pinfunction "2_2") (pintype "passive"))
      (node (ref "U1") (pin "23") (pinfunction "TDO/PCINT20_23") (pintype "bidirectional"))
      (node (ref "U12") (pin "1") (pinfunction "~{CS}_1") (pintype "bidirectional"))
    )
    (net (code "60") (name "D22") (class "Default")
      (node (ref "R14") (pin "2") (pinfunction "2_2") (pintype "passive"))
      (node (ref "U1") (pin "25") (pinfunction "TOSC1/PCINT22_25") (pintype "bidirectional"))
      (node (ref "U10") (pin "3") (pinfunction "EN_3") (pintype "bidirectional"))
      (node (ref "U5") (pin "3") (pinfunction "CE_3") (pintype "bidirectional"))
      (node (ref "U8") (pin "6") (pinfunction "EN_6") (pintype "bidirectional"))
    )
    (net (code "61") (name "D23") (class "Default")
      (node (ref "H7-H8") (pin "9") (pinfunction "DTR_9") (pintype "bidirectional"))
      (node (ref "U1") (pin "26") (pinfunction "TOSC2/PCINT23_26") (pintype "bidirectional"))
    )
    (net (code "62") (name "GND") (class "Default")
      (node (ref "BAT1") (pin "-") (pinfunction "V-_-") (pintype "bidirectional"))
      (node (ref "C1") (pin "1") (pinfunction "1_1") (pintype "passive"))
      (node (ref "C10") (pin "1") (pinfunction "1_1") (pintype "passive"))
      (node (ref "C11") (pin "1") (pinfunction "1_1") (pintype "passive"))
      (node (ref "C12") (pin "1") (pinfunction "1_1") (pintype "passive"))
      (node (ref "C13") (pin "2") (pinfunction "2_2") (pintype "passive"))
      (node (ref "C15") (pin "1") (pinfunction "1_1") (pintype "passive"))
      (node (ref "C16") (pin "1") (pinfunction "1_1") (pintype "passive"))
      (node (ref "C17") (pin "2") (pinfunction "2_2") (pintype "passive"))
      (node (ref "C18") (pin "2") (pinfunction "2_2") (pintype "passive"))
      (node (ref "C19") (pin "1") (pinfunction "1_1") (pintype "passive"))
      (node (ref "C2") (pin "1") (pinfunction "1_1") (pintype "passive"))
      (node (ref "C20") (pin "1") (pinfunction "1_1") (pintype "passive"))
      (node (ref "C21") (pin "1") (pinfunction "1_1") (pintype "passive"))
      (node (ref "C22") (pin "1") (pinfunction "1_1") (pintype "passive"))
      (node (ref "C23") (pin "1") (pinfunction "1_1") (pintype "passive"))
      (node (ref "C24") (pin "1") (pinfunction "1_1") (pintype "passive"))
      (node (ref "C25") (pin "1") (pinfunction "1_1") (pintype "passive"))
      (node (ref "C26") (pin "1") (pinfunction "1_1") (pintype "passive"))
      (node (ref "C27") (pin "1") (pinfunction "1_1") (pintype "passive"))
      (node (ref "C28") (pin "1") (pinfunction "1_1") (pintype "passive"))
      (node (ref "C29") (pin "1") (pinfunction "1_1") (pintype "passive"))
      (node (ref "C3") (pin "1") (pinfunction "1_1") (pintype "passive"))
      (node (ref "C30") (pin "1") (pinfunction "1_1") (pintype "passive"))
      (node (ref "C31") (pin "1") (pinfunction "1_1") (pintype "passive"))
      (node (ref "C32") (pin "1") (pinfunction "1_1") (pintype "passive"))
      (node (ref "C33") (pin "1") (pinfunction "1_1") (pintype "passive"))
      (node (ref "C34") (pin "1") (pinfunction "1_1") (pintype "passive"))
      (node (ref "C35") (pin "1") (pinfunction "1_1") (pintype "passive"))
      (node (ref "C36") (pin "1") (pinfunction "1_1") (pintype "passive"))
      (node (ref "C37") (pin "1") (pinfunction "1_1") (pintype "passive"))
      (node (ref "C39") (pin "2") (pinfunction "2_2") (pintype "passive"))
      (node (ref "C40") (pin "1") (pinfunction "1_1") (pintype "passive"))
      (node (ref "C5") (pin "1") (pinfunction "1_1") (pintype "passive"))
      (node (ref "C6") (pin "1") (pinfunction "1_1") (pintype "passive"))
      (node (ref "C7") (pin "2") (pinfunction "2_2") (pintype "passive"))
      (node (ref "C8") (pin "1") (pinfunction "1_1") (pintype "passive"))
      (node (ref "C9") (pin "1") (pinfunction "1_1") (pintype "passive"))
      (node (ref "D6") (pin "1") (pinfunction "1_1") (pintype "passive"))
      (node (ref "H1") (pin "20") (pinfunction "20_20") (pintype "bidirectional"))
      (node (ref "H2") (pin "20") (pinfunction "20_20") (pintype "bidirectional"))
      (node (ref "H3") (pin "5") (pinfunction "5_5") (pintype "passive"))
      (node (ref "H3") (pin "6") (pinfunction "6_6") (pintype "passive"))
      (node (ref "H4") (pin "6") (pinfunction "6_6") (pintype "bidirectional"))
      (node (ref "H5") (pin "4") (pinfunction "4_4") (pintype "bidirectional"))
      (node (ref "H6") (pin "4") (pinfunction "4_4") (pintype "bidirectional"))
      (node (ref "H7-H8") (pin "10") (pinfunction "GND_10") (pintype "power_in"))
      (node (ref "J1") (pin "2") (pinfunction "2_2") (pintype "bidirectional"))
      (node (ref "J10") (pin "4") (pinfunction "4_4") (pintype "bidirectional"))
      (node (ref "J11") (pin "4") (pinfunction "4_4") (pintype "bidirectional"))
      (node (ref "J12") (pin "4") (pinfunction "4_4") (pintype "bidirectional"))
      (node (ref "J13") (pin "4") (pinfunction "4_4") (pintype "bidirectional"))
      (node (ref "J14") (pin "4") (pinfunction "4_4") (pintype "bidirectional"))
      (node (ref "J15") (pin "1") (pinfunction "1_1") (pintype "power_in"))
      (node (ref "J16") (pin "1") (pinfunction "1_1") (pintype "power_in"))
      (node (ref "J2") (pin "2") (pinfunction "2_2") (pintype "bidirectional"))
      (node (ref "J3") (pin "2") (pinfunction "2_2") (pintype "bidirectional"))
      (node (ref "J4") (pin "2") (pinfunction "2_2") (pintype "bidirectional"))
      (node (ref "J5") (pin "6") (pinfunction "VSS_6") (pintype "bidirectional"))
      (node (ref "J5") (pin "G1") (pinfunction "G1_G1") (pintype "bidirectional"))
      (node (ref "J5") (pin "G2") (pinfunction "G2_G2") (pintype "bidirectional"))
      (node (ref "J5") (pin "G3") (pinfunction "G3_G3") (pintype "bidirectional"))
      (node (ref "J5") (pin "G4") (pinfunction "G4_G4") (pintype "bidirectional"))
      (node (ref "J6") (pin "A1/B12") (pinfunction "GND_A1/B12") (pintype "power_in"))
      (node (ref "J6") (pin "B1/A12") (pinfunction "GND_B1/A12") (pintype "power_in"))
      (node (ref "J6") (pin "G1") (pinfunction "GND_G1") (pintype "power_in"))
      (node (ref "J6") (pin "G2") (pinfunction "GND_G2") (pintype "power_in"))
      (node (ref "J6") (pin "G3") (pinfunction "GND_G3") (pintype "power_in"))
      (node (ref "J6") (pin "G4") (pinfunction "GND_G4") (pintype "power_in"))
      (node (ref "J7") (pin "5") (pinfunction "J_5") (pintype "passive"))
      (node (ref "J8") (pin "4") (pinfunction "4_4") (pintype "bidirectional"))
      (node (ref "J9") (pin "4") (pinfunction "4_4") (pintype "bidirectional"))
      (node (ref "LED10") (pin "C") (pinfunction "C_C") (pintype "passive"))
      (node (ref "LED2") (pin "C") (pinfunction "C_C") (pintype "passive"))
      (node (ref "LED3") (pin "C") (pinfunction "C_C") (pintype "passive"))
      (node (ref "LED7") (pin "C") (pinfunction "C_C") (pintype "passive"))
      (node (ref "LED8") (pin "C") (pinfunction "C_C") (pintype "passive"))
      (node (ref "LED9") (pin "C") (pinfunction "C_C") (pintype "passive"))
      (node (ref "R13") (pin "1") (pinfunction "1_1") (pintype "passive"))
      (node (ref "R14") (pin "1") (pinfunction "1_1") (pintype "passive"))
      (node (ref "R15") (pin "1") (pinfunction "1_1") (pintype "passive"))
      (node (ref "R16") (pin "2") (pinfunction "2_2") (pintype "passive"))
      (node (ref "R2") (pin "1") (pinfunction "1_1") (pintype "passive"))
      (node (ref "R25") (pin "1") (pinfunction "1_1") (pintype "passive"))
      (node (ref "R26") (pin "1") (pinfunction "1_1") (pintype "passive"))
      (node (ref "R27") (pin "1") (pinfunction "1_1") (pintype "passive"))
      (node (ref "R28") (pin "2") (pinfunction "2_2") (pintype "passive"))
      (node (ref "R30") (pin "2") (pinfunction "2_2") (pintype "passive"))
      (node (ref "R33") (pin "1") (pinfunction "1_1") (pintype "passive"))
      (node (ref "R35") (pin "1") (pinfunction "1_1") (pintype "passive"))
      (node (ref "R37") (pin "1") (pinfunction "1_1") (pintype "passive"))
      (node (ref "R38") (pin "1") (pinfunction "1_1") (pintype "passive"))
      (node (ref "R40") (pin "1") (pinfunction "1_1") (pintype "passive"))
      (node (ref "R41") (pin "1") (pinfunction "1_1") (pintype "passive"))
      (node (ref "R43") (pin "2") (pinfunction "2_2") (pintype "passive"))
      (node (ref "R6") (pin "1") (pinfunction "1_1") (pintype "passive"))
      (node (ref "S3") (pin "1") (pinfunction "1_1") (pintype "passive"))
      (node (ref "S3") (pin "2") (pinfunction "2_2") (pintype "passive"))
      (node (ref "SJ14") (pin "2") (pinfunction "2_2") (pintype "passive"))
      (node (ref "SJ15") (pin "1") (pinfunction "1_1") (pintype "passive"))
      (node (ref "U1") (pin "18") (pinfunction "GND_2_18") (pintype "bidirectional"))
      (node (ref "U1") (pin "28") (pinfunction "GND_3_28") (pintype "bidirectional"))
      (node (ref "U1") (pin "39") (pinfunction "GND_4_39") (pintype "bidirectional"))
      (node (ref "U1") (pin "6") (pinfunction "GND_1_6") (pintype "bidirectional"))
      (node (ref "U10") (pin "13") (pinfunction "PGND_1_13") (pintype "bidirectional"))
      (node (ref "U10") (pin "14") (pinfunction "PGND_2_14") (pintype "bidirectional"))
      (node (ref "U10") (pin "15") (pinfunction "EP_15") (pintype "bidirectional"))
      (node (ref "U10") (pin "6") (pinfunction "AGND_6") (pintype "bidirectional"))
      (node (ref "U12") (pin "4") (pinfunction "GND_4") (pintype "bidirectional"))
      (node (ref "U13") (pin "4") (pinfunction "VSS_4") (pintype "passive"))
      (node (ref "U14") (pin "4") (pinfunction "GND_4") (pintype "bidirectional"))
      (node (ref "U2") (pin "5") (pinfunction "GND_5") (pintype "bidirectional"))
      (node (ref "U3") (pin "12") (pinfunction "GND_2_12") (pintype "bidirectional"))
      (node (ref "U3") (pin "21") (pinfunction "EP_GND_21") (pintype "bidirectional"))
      (node (ref "U3") (pin "3") (pinfunction "GND_1_3") (pintype "bidirectional"))
      (node (ref "U4") (pin "2") (pinfunction "VSS_2") (pintype "bidirectional"))
      (node (ref "U5") (pin "2") (pinfunction "VSS_2") (pintype "bidirectional"))
      (node (ref "U6") (pin "2") (pinfunction "VSS_2") (pintype "bidirectional"))
      (node (ref "U7") (pin "3") (pinfunction "GND_3") (pintype "bidirectional"))
      (node (ref "U8") (pin "3") (pinfunction "GND_3") (pintype "bidirectional"))
      (node (ref "U8") (pin "4") (pinfunction "SEL_4") (pintype "bidirectional"))
      (node (ref "U9") (pin "14") (pinfunction "TMR_14") (pintype "input"))
      (node (ref "U9") (pin "6") (pinfunction "EN1_6") (pintype "input"))
      (node (ref "U9") (pin "8") (pinfunction "VSS_8") (pintype "power_in"))
      (node (ref "U9") (pin "THERMAL") (pinfunction "VSS_THERMAL") (pintype "power_in"))
      (node (ref "Y1") (pin "2") (pinfunction "2_2") (pintype "passive"))
    )
    (net (code "63") (name "Net-(C38-Pad1)") (class "Default")
      (node (ref "C38") (pin "1") (pinfunction "1_1") (pintype "passive"))
      (node (ref "R18") (pin "2") (pinfunction "2_2") (pintype "passive"))
      (node (ref "R19") (pin "1") (pinfunction "1_1") (pintype "passive"))
      (node (ref "SJ25") (pin "2") (pinfunction "2_2") (pintype "passive"))
    )
    (net (code "64") (name "Net-(H5-Pad3)") (class "Default")
      (node (ref "H5") (pin "3") (pinfunction "3_3") (pintype "bidirectional"))
      (node (ref "J13") (pin "3") (pinfunction "3_3") (pintype "bidirectional"))
      (node (ref "JP5") (pin "2") (pinfunction "2_2") (pintype "bidirectional"))
    )
    (net (code "65") (name "Net-(H6-Pad3)") (class "Default")
      (node (ref "H6") (pin "3") (pinfunction "3_3") (pintype "bidirectional"))
      (node (ref "J10") (pin "3") (pinfunction "3_3") (pintype "bidirectional"))
      (node (ref "JP2") (pin "2") (pinfunction "2_2") (pintype "bidirectional"))
    )
    (net (code "66") (name "Net-(H7-H8-BEE_CTS)") (class "Default")
      (node (ref "H7-H8") (pin "12") (pinfunction "BEE_CTS_12") (pintype "output"))
      (node (ref "SJ19") (pin "3") (pinfunction "3_3") (pintype "passive"))
    )
    (net (code "67") (name "Net-(H7-H8-DIO5)") (class "Default")
      (node (ref "H7-H8") (pin "15") (pinfunction "DIO5_15") (pintype "bidirectional"))
      (node (ref "SJ17") (pin "2") (pinfunction "2_2") (pintype "passive"))
    )
    (net (code "68") (name "Net-(H7-H8-DIO9)") (class "Default")
      (node (ref "H7-H8") (pin "13") (pinfunction "DIO9_13") (pintype "bidirectional"))
      (node (ref "SJ19") (pin "1") (pinfunction "1_1") (pintype "passive"))
    )
    (net (code "69") (name "Net-(H7-H8-RESET)") (class "Default")
      (node (ref "C3") (pin "2") (pinfunction "2_2") (pintype "passive"))
      (node (ref "H7-H8") (pin "5") (pinfunction "RESET_5") (pintype "input"))
      (node (ref "R42") (pin "1") (pinfunction "1_1") (pintype "passive"))
      (node (ref "SJ20") (pin "3") (pinfunction "3_3") (pintype "passive"))
    )
    (net (code "70") (name "Net-(J6-CC1)") (class "Default")
      (node (ref "J6") (pin "A5") (pinfunction "CC1_A5") (pintype "bidirectional"))
      (node (ref "R28") (pin "1") (pinfunction "1_1") (pintype "passive"))
    )
    (net (code "71") (name "Net-(J6-CC2)") (class "Default")
      (node (ref "J6") (pin "B5") (pinfunction "CC2_B5") (pintype "bidirectional"))
      (node (ref "R30") (pin "1") (pinfunction "1_1") (pintype "passive"))
    )
    (net (code "72") (name "Net-(J8-Pad3)") (class "Default")
      (node (ref "J8") (pin "3") (pinfunction "3_3") (pintype "bidirectional"))
      (node (ref "J9") (pin "3") (pinfunction "3_3") (pintype "bidirectional"))
      (node (ref "JP1") (pin "2") (pinfunction "2_2") (pintype "bidirectional"))
    )
    (net (code "73") (name "Net-(J11-Pad3)") (class "Default")
      (node (ref "J11") (pin "3") (pinfunction "3_3") (pintype "bidirectional"))
      (node (ref "JP4") (pin "2") (pinfunction "2_2") (pintype "bidirectional"))
    )
    (net (code "74") (name "Net-(J12-Pad3)") (class "Default")
      (node (ref "J12") (pin "3") (pinfunction "3_3") (pintype "bidirectional"))
      (node (ref "JP3") (pin "2") (pinfunction "2_2") (pintype "bidirectional"))
    )
    (net (code "75") (name "Net-(LED1-PadC)") (class "Default")
      (node (ref "LED1") (pin "C") (pinfunction "C_C") (pintype "passive"))
      (node (ref "R27") (pin "2") (pinfunction "2_2") (pintype "passive"))
    )
    (net (code "76") (name "Net-(LED2-PadA)") (class "Default")
      (node (ref "LED2") (pin "A") (pinfunction "A_A") (pintype "passive"))
      (node (ref "R29") (pin "2") (pinfunction "2_2") (pintype "passive"))
    )
    (net (code "77") (name "Net-(LED3-PadA)") (class "Default")
      (node (ref "LED3") (pin "A") (pinfunction "A_A") (pintype "passive"))
      (node (ref "R12") (pin "1") (pinfunction "1_1") (pintype "passive"))
    )
    (net (code "78") (name "Net-(LED4-PadA)") (class "Default")
      (node (ref "LED4") (pin "A") (pinfunction "A_A") (pintype "passive"))
      (node (ref "R4") (pin "2") (pinfunction "2_2") (pintype "passive"))
    )
    (net (code "79") (name "Net-(LED5-PadA)") (class "Default")
      (node (ref "LED5") (pin "A") (pinfunction "A_A") (pintype "passive"))
      (node (ref "R22") (pin "2") (pinfunction "2_2") (pintype "passive"))
    )
    (net (code "80") (name "Net-(LED6-PadA)") (class "Default")
      (node (ref "LED6") (pin "A") (pinfunction "A_A") (pintype "passive"))
      (node (ref "R23") (pin "2") (pinfunction "2_2") (pintype "passive"))
    )
    (net (code "81") (name "Net-(LED7-PadA)") (class "Default")
      (node (ref "LED7") (pin "A") (pinfunction "A_A") (pintype "passive"))
      (node (ref "R32") (pin "1") (pinfunction "1_1") (pintype "passive"))
    )
    (net (code "82") (name "Net-(LED8-PadA)") (class "Default")
      (node (ref "LED8") (pin "A") (pinfunction "A_A") (pintype "passive"))
      (node (ref "R8") (pin "2") (pinfunction "2_2") (pintype "passive"))
    )
    (net (code "83") (name "Net-(LED9-PadA)") (class "Default")
      (node (ref "LED9") (pin "A") (pinfunction "A_A") (pintype "passive"))
      (node (ref "R9") (pin "2") (pinfunction "2_2") (pintype "passive"))
    )
    (net (code "84") (name "Net-(LED10-PadA)") (class "Default")
      (node (ref "LED10") (pin "A") (pinfunction "A_A") (pintype "passive"))
      (node (ref "R36") (pin "2") (pinfunction "2_2") (pintype "passive"))
    )
    (net (code "85") (name "Net-(Q2-S)") (class "Default")
      (node (ref "C9") (pin "2") (pinfunction "2_2") (pintype "passive"))
      (node (ref "D4") (pin "1") (pinfunction "1_1") (pintype "passive"))
      (node (ref "Q2") (pin "2") (pinfunction "S_2") (pintype "passive"))
      (node (ref "U5") (pin "1") (pinfunction "VIN_1") (pintype "bidirectional"))
    )
    (net (code "86") (name "Net-(Q3-S)") (class "Default")
      (node (ref "C21") (pin "2") (pinfunction "2_2") (pintype "passive"))
      (node (ref "D5") (pin "1") (pinfunction "1_1") (pintype "passive"))
      (node (ref "Q3") (pin "2") (pinfunction "S_2") (pintype "passive"))
      (node (ref "U6") (pin "1") (pinfunction "VIN_1") (pintype "bidirectional"))
    )
    (net (code "87") (name "Net-(Q4-C)") (class "Default")
      (node (ref "Q4") (pin "1") (pinfunction "C_1") (pintype "passive"))
      (node (ref "SJ23") (pin "2") (pinfunction "2_2") (pintype "passive"))
    )
    (net (code "88") (name "Net-(Q4-E)") (class "Default")
      (node (ref "Q4") (pin "2") (pinfunction "E_2") (pintype "passive"))
      (node (ref "R43") (pin "1") (pinfunction "1_1") (pintype "passive"))
      (node (ref "SJ24") (pin "1") (pinfunction "1_1") (pintype "passive"))
    )
    (net (code "89") (name "Net-(R4-Pad1)") (class "Default")
      (node (ref "R4") (pin "1") (pinfunction "1_1") (pintype "passive"))
      (node (ref "SJ4") (pin "2") (pinfunction "2_2") (pintype "passive"))
    )
    (net (code "90") (name "Net-(R5-Pad1)") (class "Default")
      (node (ref "R5") (pin "1") (pinfunction "1_1") (pintype "passive"))
      (node (ref "SJ14") (pin "1") (pinfunction "1_1") (pintype "passive"))
    )
    (net (code "91") (name "Net-(R11-Pad2)") (class "Default")
      (node (ref "R11") (pin "2") (pinfunction "2_2") (pintype "passive"))
      (node (ref "SJ2") (pin "1") (pinfunction "1_1") (pintype "passive"))
    )
    (net (code "92") (name "Net-(R12-Pad2)") (class "Default")
      (node (ref "R12") (pin "2") (pinfunction "2_2") (pintype "passive"))
      (node (ref "SJ3") (pin "2") (pinfunction "2_2") (pintype "passive"))
    )
    (net (code "93") (name "Net-(R20-Pad1)") (class "Default")
      (node (ref "R20") (pin "1") (pinfunction "1_1") (pintype "passive"))
      (node (ref "SJ12") (pin "2") (pinfunction "2_2") (pintype "passive"))
    )
    (net (code "94") (name "Net-(R31-Pad1)") (class "Default")
      (node (ref "R31") (pin "1") (pinfunction "1_1") (pintype "passive"))
      (node (ref "SJ25") (pin "1") (pinfunction "1_1") (pintype "passive"))
    )
    (net (code "95") (name "Net-(R32-Pad2)") (class "Default")
      (node (ref "R32") (pin "2") (pinfunction "2_2") (pintype "passive"))
      (node (ref "SJ16") (pin "2") (pinfunction "2_2") (pintype "passive"))
    )
    (net (code "96") (name "Net-(R36-Pad1)") (class "Default")
      (node (ref "R36") (pin "1") (pinfunction "1_1") (pintype "passive"))
      (node (ref "SJ17") (pin "1") (pinfunction "1_1") (pintype "passive"))
    )
    (net (code "97") (name "Net-(R39-Pad1)") (class "Default")
      (node (ref "R39") (pin "1") (pinfunction "1_1") (pintype "passive"))
      (node (ref "SJ15") (pin "2") (pinfunction "2_2") (pintype "passive"))
    )
    (net (code "98") (name "Net-(R42-Pad2)") (class "Default")
      (node (ref "R42") (pin "2") (pinfunction "2_2") (pintype "passive"))
      (node (ref "SJ21") (pin "1") (pinfunction "1_1") (pintype "passive"))
    )
    (net (code "99") (name "Net-(S2-NO_1)") (class "Default")
      (node (ref "R11") (pin "1") (pinfunction "1_1") (pintype "passive"))
      (node (ref "R13") (pin "2") (pinfunction "2_2") (pintype "passive"))
      (node (ref "S2") (pin "1") (pinfunction "NO_1_1") (pintype "bidirectional"))
      (node (ref "S2") (pin "2") (pinfunction "NO_2_2") (pintype "bidirectional"))
    )
    (net (code "100") (name "Net-(S4-NO1)") (class "Default")
      (node (ref "LED1") (pin "A") (pinfunction "A_A") (pintype "passive"))
      (node (ref "S4") (pin "1B") (pinfunction "NO1_1B") (pintype "passive"))
    )
    (net (code "101") (name "Net-(U1-XTAL1)") (class "Default")
      (node (ref "U1") (pin "8") (pinfunction "XTAL1_8") (pintype "bidirectional"))
      (node (ref "Y1") (pin "1") (pinfunction "1_1") (pintype "passive"))
    )
    (net (code "102") (name "Net-(U1-XTAL2)") (class "Default")
      (node (ref "U1") (pin "7") (pinfunction "XTAL2_7") (pintype "bidirectional"))
      (node (ref "Y1") (pin "3") (pinfunction "3_3") (pintype "passive"))
    )
    (net (code "103") (name "Net-(U2-SQW{slash}INT)") (class "Default")
      (node (ref "SJ1") (pin "2") (pinfunction "2_2") (pintype "passive"))
      (node (ref "U2") (pin "3") (pinfunction "SQW/INT_3") (pintype "bidirectional"))
    )
    (net (code "104") (name "Net-(U2-VBAT)") (class "Default")
      (node (ref "BAT1") (pin "+1") (pinfunction "V+_+1") (pintype "bidirectional"))
      (node (ref "BAT1") (pin "+2") (pinfunction "V+_+2") (pintype "bidirectional"))
      (node (ref "U2") (pin "6") (pinfunction "VBAT_6") (pintype "bidirectional"))
    )
    (net (code "105") (name "Net-(U3-GPIO.2_{slash}_TXT)") (class "Default")
      (node (ref "LED5") (pin "C") (pinfunction "C_C") (pintype "passive"))
      (node (ref "U3") (pin "20") (pinfunction "GPIO.2_/_TXT_20") (pintype "bidirectional"))
    )
    (net (code "106") (name "Net-(U3-GPIO.3_{slash}_RXT)") (class "Default")
      (node (ref "LED6") (pin "C") (pinfunction "C_C") (pintype "passive"))
      (node (ref "U3") (pin "19") (pinfunction "GPIO.3_/_RXT_19") (pintype "bidirectional"))
    )
    (net (code "107") (name "Net-(U3-RSTB)") (class "Default")
      (node (ref "R21") (pin "1") (pinfunction "1_1") (pintype "passive"))
      (node (ref "U3") (pin "9") (pinfunction "RSTB_9") (pintype "bidirectional"))
    )
    (net (code "108") (name "Net-(U3-VBUS)") (class "Default")
      (node (ref "R24") (pin "1") (pinfunction "1_1") (pintype "passive"))
      (node (ref "R25") (pin "2") (pinfunction "2_2") (pintype "passive"))
      (node (ref "U3") (pin "8") (pinfunction "VBUS_8") (pintype "bidirectional"))
    )
    (net (code "109") (name "Net-(U4-CE)") (class "Default")
      (node (ref "H10") (pin "1") (pinfunction "1_1") (pintype "passive"))
      (node (ref "R26") (pin "2") (pinfunction "2_2") (pintype "passive"))
      (node (ref "S1") (pin "COM1") (pinfunction "COM1_COM1") (pintype "bidirectional"))
      (node (ref "U4") (pin "3") (pinfunction "CE_3") (pintype "bidirectional"))
    )
    (net (code "110") (name "Net-(U6-CE)") (class "Default")
      (node (ref "SJ18") (pin "2") (pinfunction "2_2") (pintype "passive"))
      (node (ref "U6") (pin "3") (pinfunction "CE_3") (pintype "bidirectional"))
    )
    (net (code "111") (name "Net-(U8-LX)") (class "Default")
      (node (ref "L2") (pin "2") (pinfunction "2_2") (pintype "bidirectional"))
      (node (ref "U8") (pin "2") (pinfunction "LX_2") (pintype "bidirectional"))
    )
    (net (code "112") (name "Net-(U9-ILIM)") (class "Default")
      (node (ref "R41") (pin "2") (pinfunction "2_2") (pintype "passive"))
      (node (ref "R5") (pin "2") (pinfunction "2_2") (pintype "passive"))
      (node (ref "U9") (pin "12") (pinfunction "ILIM_12") (pintype "input"))
    )
    (net (code "113") (name "Net-(U9-IN)") (class "Default")
      (node (ref "C2") (pin "2") (pinfunction "2_2") (pintype "passive"))
      (node (ref "C33") (pin "2") (pinfunction "2_2") (pintype "passive"))
      (node (ref "D1") (pin "1") (pinfunction "1_1") (pintype "passive"))
      (node (ref "D2") (pin "1") (pinfunction "1_1") (pintype "passive"))
      (node (ref "U9") (pin "13") (pinfunction "IN_13") (pintype "power_in"))
    )
    (net (code "114") (name "Net-(U9-ISET)") (class "Default")
      (node (ref "R39") (pin "2") (pinfunction "2_2") (pintype "passive"))
      (node (ref "R40") (pin "2") (pinfunction "2_2") (pintype "passive"))
      (node (ref "U9") (pin "16") (pinfunction "ISET_16") (pintype "input"))
    )
    (net (code "115") (name "Net-(U9-ITERM)") (class "Default")
      (node (ref "R37") (pin "2") (pinfunction "2_2") (pintype "passive"))
      (node (ref "U9") (pin "15") (pinfunction "ITERM_15") (pintype "input"))
    )
    (net (code "116") (name "Net-(U9-TS)") (class "Default")
      (node (ref "R35") (pin "2") (pinfunction "2_2") (pintype "passive"))
      (node (ref "U9") (pin "1") (pinfunction "TS_1") (pintype "input"))
    )
    (net (code "117") (name "Net-(U9-~{CE})") (class "Default")
      (node (ref "R38") (pin "2") (pinfunction "2_2") (pintype "passive"))
      (node (ref "U9") (pin "4") (pinfunction "~{CE}_4") (pintype "input"))
    )
    (net (code "118") (name "Net-(U9-~{CHG})") (class "Default")
      (node (ref "LED4") (pin "C") (pinfunction "C_C") (pintype "passive"))
      (node (ref "U9") (pin "9") (pinfunction "~{CHG}_9") (pintype "output"))
    )
    (net (code "119") (name "Net-(U10-BST)") (class "Default")
      (node (ref "C41") (pin "2") (pinfunction "2_2") (pintype "passive"))
      (node (ref "U10") (pin "7") (pinfunction "BST_7") (pintype "bidirectional"))
    )
    (net (code "120") (name "Net-(U10-FB)") (class "Default")
      (node (ref "R15") (pin "2") (pinfunction "2_2") (pintype "passive"))
      (node (ref "R19") (pin "2") (pinfunction "2_2") (pintype "passive"))
      (node (ref "R31") (pin "2") (pinfunction "2_2") (pintype "passive"))
      (node (ref "U10") (pin "4") (pinfunction "FB_4") (pintype "bidirectional"))
    )
    (net (code "121") (name "Net-(U10-ISET)") (class "Default")
      (node (ref "C40") (pin "2") (pinfunction "2_2") (pintype "passive"))
      (node (ref "U10") (pin "1") (pinfunction "VL_1") (pintype "bidirectional"))
      (node (ref "U10") (pin "5") (pinfunction "ISET_5") (pintype "bidirectional"))
    )
    (net (code "122") (name "Net-(U10-LX_1)") (class "Default")
      (node (ref "C41") (pin "1") (pinfunction "1_1") (pintype "passive"))
      (node (ref "L1") (pin "2") (pinfunction "2_2") (pintype "bidirectional"))
      (node (ref "U10") (pin "11") (pinfunction "LX_1_11") (pintype "bidirectional"))
      (node (ref "U10") (pin "12") (pinfunction "LX_2_12") (pintype "bidirectional"))
    )
    (net (code "123") (name "Net-(U10-PVH_1)") (class "Default")
      (node (ref "C20") (pin "2") (pinfunction "2_2") (pintype "passive"))
      (node (ref "C35") (pin "2") (pinfunction "2_2") (pintype "passive"))
      (node (ref "C38") (pin "2") (pinfunction "2_2") (pintype "passive"))
      (node (ref "U10") (pin "10") (pinfunction "PVH_2_10") (pintype "bidirectional"))
      (node (ref "U10") (pin "9") (pinfunction "PVH_1_9") (pintype "bidirectional"))
    )
    (net (code "124") (name "Net-(U13-VDD)") (class "Default")
      (node (ref "SJ22") (pin "2") (pinfunction "2_2") (pintype "passive"))
      (node (ref "U13") (pin "3") (pinfunction "VDD_3") (pintype "power_in"))
    )
    (net (code "125") (name "RESET") (class "Default")
      (node (ref "C14") (pin "1") (pinfunction "1_1") (pintype "passive"))
      (node (ref "C4") (pin "2") (pinfunction "2_2") (pintype "passive"))
      (node (ref "H4") (pin "5") (pinfunction "5_5") (pintype "bidirectional"))
      (node (ref "R3") (pin "1") (pinfunction "1_1") (pintype "passive"))
      (node (ref "S3") (pin "3") (pinfunction "3_3") (pintype "passive"))
      (node (ref "S3") (pin "4") (pinfunction "4_4") (pintype "passive"))
      (node (ref "U1") (pin "4") (pinfunction "~{RESET}_4") (pintype "bidirectional"))
    )
    (net (code "126") (name "VUSB") (class "Default")
      (node (ref "D1") (pin "2") (pinfunction "2_2") (pintype "passive"))
      (node (ref "D3") (pin "2") (pinfunction "2_2") (pintype "passive"))
      (node (ref "D4") (pin "2") (pinfunction "2_2") (pintype "passive"))
      (node (ref "D5") (pin "2") (pinfunction "2_2") (pintype "passive"))
      (node (ref "D6") (pin "2") (pinfunction "2_2") (pintype "passive"))
      (node (ref "H3") (pin "4") (pinfunction "4_4") (pintype "passive"))
      (node (ref "J6") (pin "A4/B9") (pinfunction "VBUS_A4/B9") (pintype "power_in"))
      (node (ref "J6") (pin "B4/A9") (pinfunction "VBUS_B4/A9") (pintype "power_in"))
      (node (ref "Q1") (pin "1") (pinfunction "G_1") (pintype "passive"))
      (node (ref "Q2") (pin "1") (pinfunction "G_1") (pintype "passive"))
      (node (ref "Q3") (pin "1") (pinfunction "G_1") (pintype "passive"))
      (node (ref "R6") (pin "2") (pinfunction "2_2") (pintype "passive"))
      (node (ref "S4") (pin "2A") (pinfunction "COM2_2A") (pintype "passive"))
    )
    (net (code "127") (name "V_BATT") (class "Default")
      (node (ref "C26") (pin "2") (pinfunction "2_2") (pintype "passive"))
      (node (ref "C27") (pin "2") (pinfunction "2_2") (pintype "passive"))
      (node (ref "C28") (pin "2") (pinfunction "2_2") (pintype "passive"))
      (node (ref "C39") (pin "1") (pinfunction "1_1") (pintype "passive"))
      (node (ref "C7") (pin "1") (pinfunction "1_1") (pintype "passive"))
      (node (ref "H2") (pin "12") (pinfunction "12_12") (pintype "bidirectional"))
      (node (ref "L1") (pin "1") (pinfunction "1_1") (pintype "bidirectional"))
      (node (ref "Q1") (pin "3") (pinfunction "D_3") (pintype "passive"))
      (node (ref "Q2") (pin "3") (pinfunction "D_3") (pintype "passive"))
      (node (ref "Q3") (pin "3") (pinfunction "D_3") (pintype "passive"))
      (node (ref "SJ4") (pin "1") (pinfunction "1_1") (pintype "passive"))
      (node (ref "U10") (pin "2") (pinfunction "IN_2") (pintype "bidirectional"))
      (node (ref "U9") (pin "10") (pinfunction "OUT_10") (pintype "output"))
      (node (ref "U9") (pin "11") (pinfunction "OUT_11") (pintype "output"))
      (node (ref "U9") (pin "5") (pinfunction "EN2_5") (pintype "input"))
    )
    (net (code "128") (name "V_SOLAR") (class "Default")
      (node (ref "D2") (pin "2") (pinfunction "2_2") (pintype "passive"))
      (node (ref "J3") (pin "1") (pinfunction "1_1") (pintype "bidirectional"))
      (node (ref "J4") (pin "1") (pinfunction "1_1") (pintype "bidirectional"))
    )
    (net (code "129") (name "unconnected-(H7-H8-DIO1-Pad19)") (class "Default")
      (node (ref "H7-H8") (pin "19") (pinfunction "DIO1_19") (pintype "bidirectional"))
    )
    (net (code "130") (name "unconnected-(H7-H8-DIO2-Pad18)") (class "Default")
      (node (ref "H7-H8") (pin "18") (pinfunction "DIO2_18") (pintype "bidirectional"))
    )
    (net (code "131") (name "unconnected-(H7-H8-DIO3-Pad17)") (class "Default")
      (node (ref "H7-H8") (pin "17") (pinfunction "DIO3_17") (pintype "bidirectional"))
    )
    (net (code "132") (name "unconnected-(H7-H8-DIO4-Pad11)") (class "Default")
      (node (ref "H7-H8") (pin "11") (pinfunction "DIO4_11") (pintype "bidirectional"))
    )
    (net (code "133") (name "unconnected-(H7-H8-DIO11-Pad7)") (class "Default")
      (node (ref "H7-H8") (pin "7") (pinfunction "DIO11_7") (pintype "bidirectional"))
    )
    (net (code "134") (name "unconnected-(H7-H8-DIO12-Pad4)") (class "Default")
      (node (ref "H7-H8") (pin "4") (pinfunction "DIO12_4") (pintype "bidirectional"))
    )
    (net (code "135") (name "unconnected-(H7-H8-RES-Pad8)") (class "Default")
      (node (ref "H7-H8") (pin "8") (pinfunction "RES_8") (pintype "bidirectional"))
    )
    (net (code "136") (name "unconnected-(H7-H8-RES-Pad14)") (class "Default")
      (node (ref "H7-H8") (pin "14") (pinfunction "RES_14") (pintype "bidirectional"))
    )
    (net (code "137") (name "unconnected-(H7-H8-RSSI-Pad6)") (class "Default")
      (node (ref "H7-H8") (pin "6") (pinfunction "RSSI_6") (pintype "bidirectional"))
    )
    (net (code "138") (name "unconnected-(J5-CDN-Pad9)") (class "Default")
      (node (ref "J5") (pin "9") (pinfunction "CDN_9") (pintype "bidirectional"))
    )
    (net (code "139") (name "unconnected-(J5-DATA1-Pad8)") (class "Default")
      (node (ref "J5") (pin "8") (pinfunction "DATA1_8") (pintype "bidirectional"))
    )
    (net (code "140") (name "unconnected-(J5-DATA2-Pad1)") (class "Default")
      (node (ref "J5") (pin "1") (pinfunction "DATA2_1") (pintype "bidirectional"))
    )
    (net (code "141") (name "unconnected-(J6-SBU1-PadA8)") (class "Default")
      (node (ref "J6") (pin "A8") (pinfunction "SBU1_A8") (pintype "bidirectional"))
    )
    (net (code "142") (name "unconnected-(J6-SBU2-PadB8)") (class "Default")
      (node (ref "J6") (pin "B8") (pinfunction "SBU2_B8") (pintype "bidirectional"))
    )
    (net (code "143") (name "unconnected-(J7G-J-Pad7)") (class "Default")
      (node (ref "J7") (pin "7") (pinfunction "J_7") (pintype "passive"))
    )
    (net (code "144") (name "unconnected-(J7H-J-Pad8)") (class "Default")
      (node (ref "J7") (pin "8") (pinfunction "J_8") (pintype "passive"))
    )
    (net (code "145") (name "unconnected-(S1-PadCH1B)") (class "Default")
      (node (ref "S1") (pin "CH1B") (pinfunction "CH1B_CH1B") (pintype "bidirectional"))
    )
    (net (code "146") (name "unconnected-(S1-PadCH2B)") (class "Default")
      (node (ref "S1") (pin "CH2B") (pinfunction "CH2B_CH2B") (pintype "bidirectional"))
    )
    (net (code "147") (name "unconnected-(U2-32KHZ-Pad1)") (class "Default")
      (node (ref "U2") (pin "1") (pinfunction "32KHZ_1") (pintype "bidirectional"))
    )
    (net (code "148") (name "unconnected-(U2-{slash}RST-Pad4)") (class "Default")
      (node (ref "U2") (pin "4") (pinfunction "/RST_4") (pintype "bidirectional"))
    )
    (net (code "149") (name "unconnected-(U3-CTS-Pad15)") (class "Default")
      (node (ref "U3") (pin "15") (pinfunction "CTS_15") (pintype "bidirectional"))
    )
    (net (code "150") (name "unconnected-(U3-GPIO.0_{slash}_CLK-Pad2)") (class "Default")
      (node (ref "U3") (pin "2") (pinfunction "GPIO.0_/_CLK_2") (pintype "bidirectional"))
    )
    (net (code "151") (name "unconnected-(U3-GPIO.1_{slash}_RS485-Pad1)") (class "Default")
      (node (ref "U3") (pin "1") (pinfunction "GPIO.1_/_RS485_1") (pintype "bidirectional"))
    )
    (net (code "152") (name "unconnected-(U3-NC-Pad10)") (class "Default")
      (node (ref "U3") (pin "10") (pinfunction "NC_10") (pintype "no_connect"))
    )
    (net (code "153") (name "unconnected-(U3-SUSPEND-Pad14)") (class "Default")
      (node (ref "U3") (pin "14") (pinfunction "SUSPEND_14") (pintype "bidirectional"))
    )
    (net (code "154") (name "unconnected-(U3-SUSPENDB-Pad11)") (class "Default")
      (node (ref "U3") (pin "11") (pinfunction "SUSPENDB_11") (pintype "bidirectional"))
    )
    (net (code "155") (name "unconnected-(U3-WAKEUP-Pad13)") (class "Default")
      (node (ref "U3") (pin "13") (pinfunction "WAKEUP_13") (pintype "bidirectional"))
    )
    (net (code "156") (name "unconnected-(U4-NC-Pad4)") (class "Default")
      (node (ref "U4") (pin "4") (pinfunction "NC_4") (pintype "no_connect"))
    )
    (net (code "157") (name "unconnected-(U5-NC-Pad4)") (class "Default")
      (node (ref "U5") (pin "4") (pinfunction "NC_4") (pintype "no_connect"))
    )
    (net (code "158") (name "unconnected-(U6-NC-Pad4)") (class "Default")
      (node (ref "U6") (pin "4") (pinfunction "NC_4") (pintype "no_connect"))
    )
    (net (code "159") (name "unconnected-(U9-~{PGOOD}-Pad7)") (class "Default")
      (node (ref "U9") (pin "7") (pinfunction "~{PGOOD}_7") (pintype "output"))
    )
    (net (code "160") (name "unconnected-(U13-NC-Pad5)") (class "Default")
      (node (ref "U13") (pin "5") (pinfunction "NC_5") (pintype "no_connect"))
    )
  )
)
